# galvanika-board-2_0.net
KiCad netlist of a schematic drawn in EAGLE
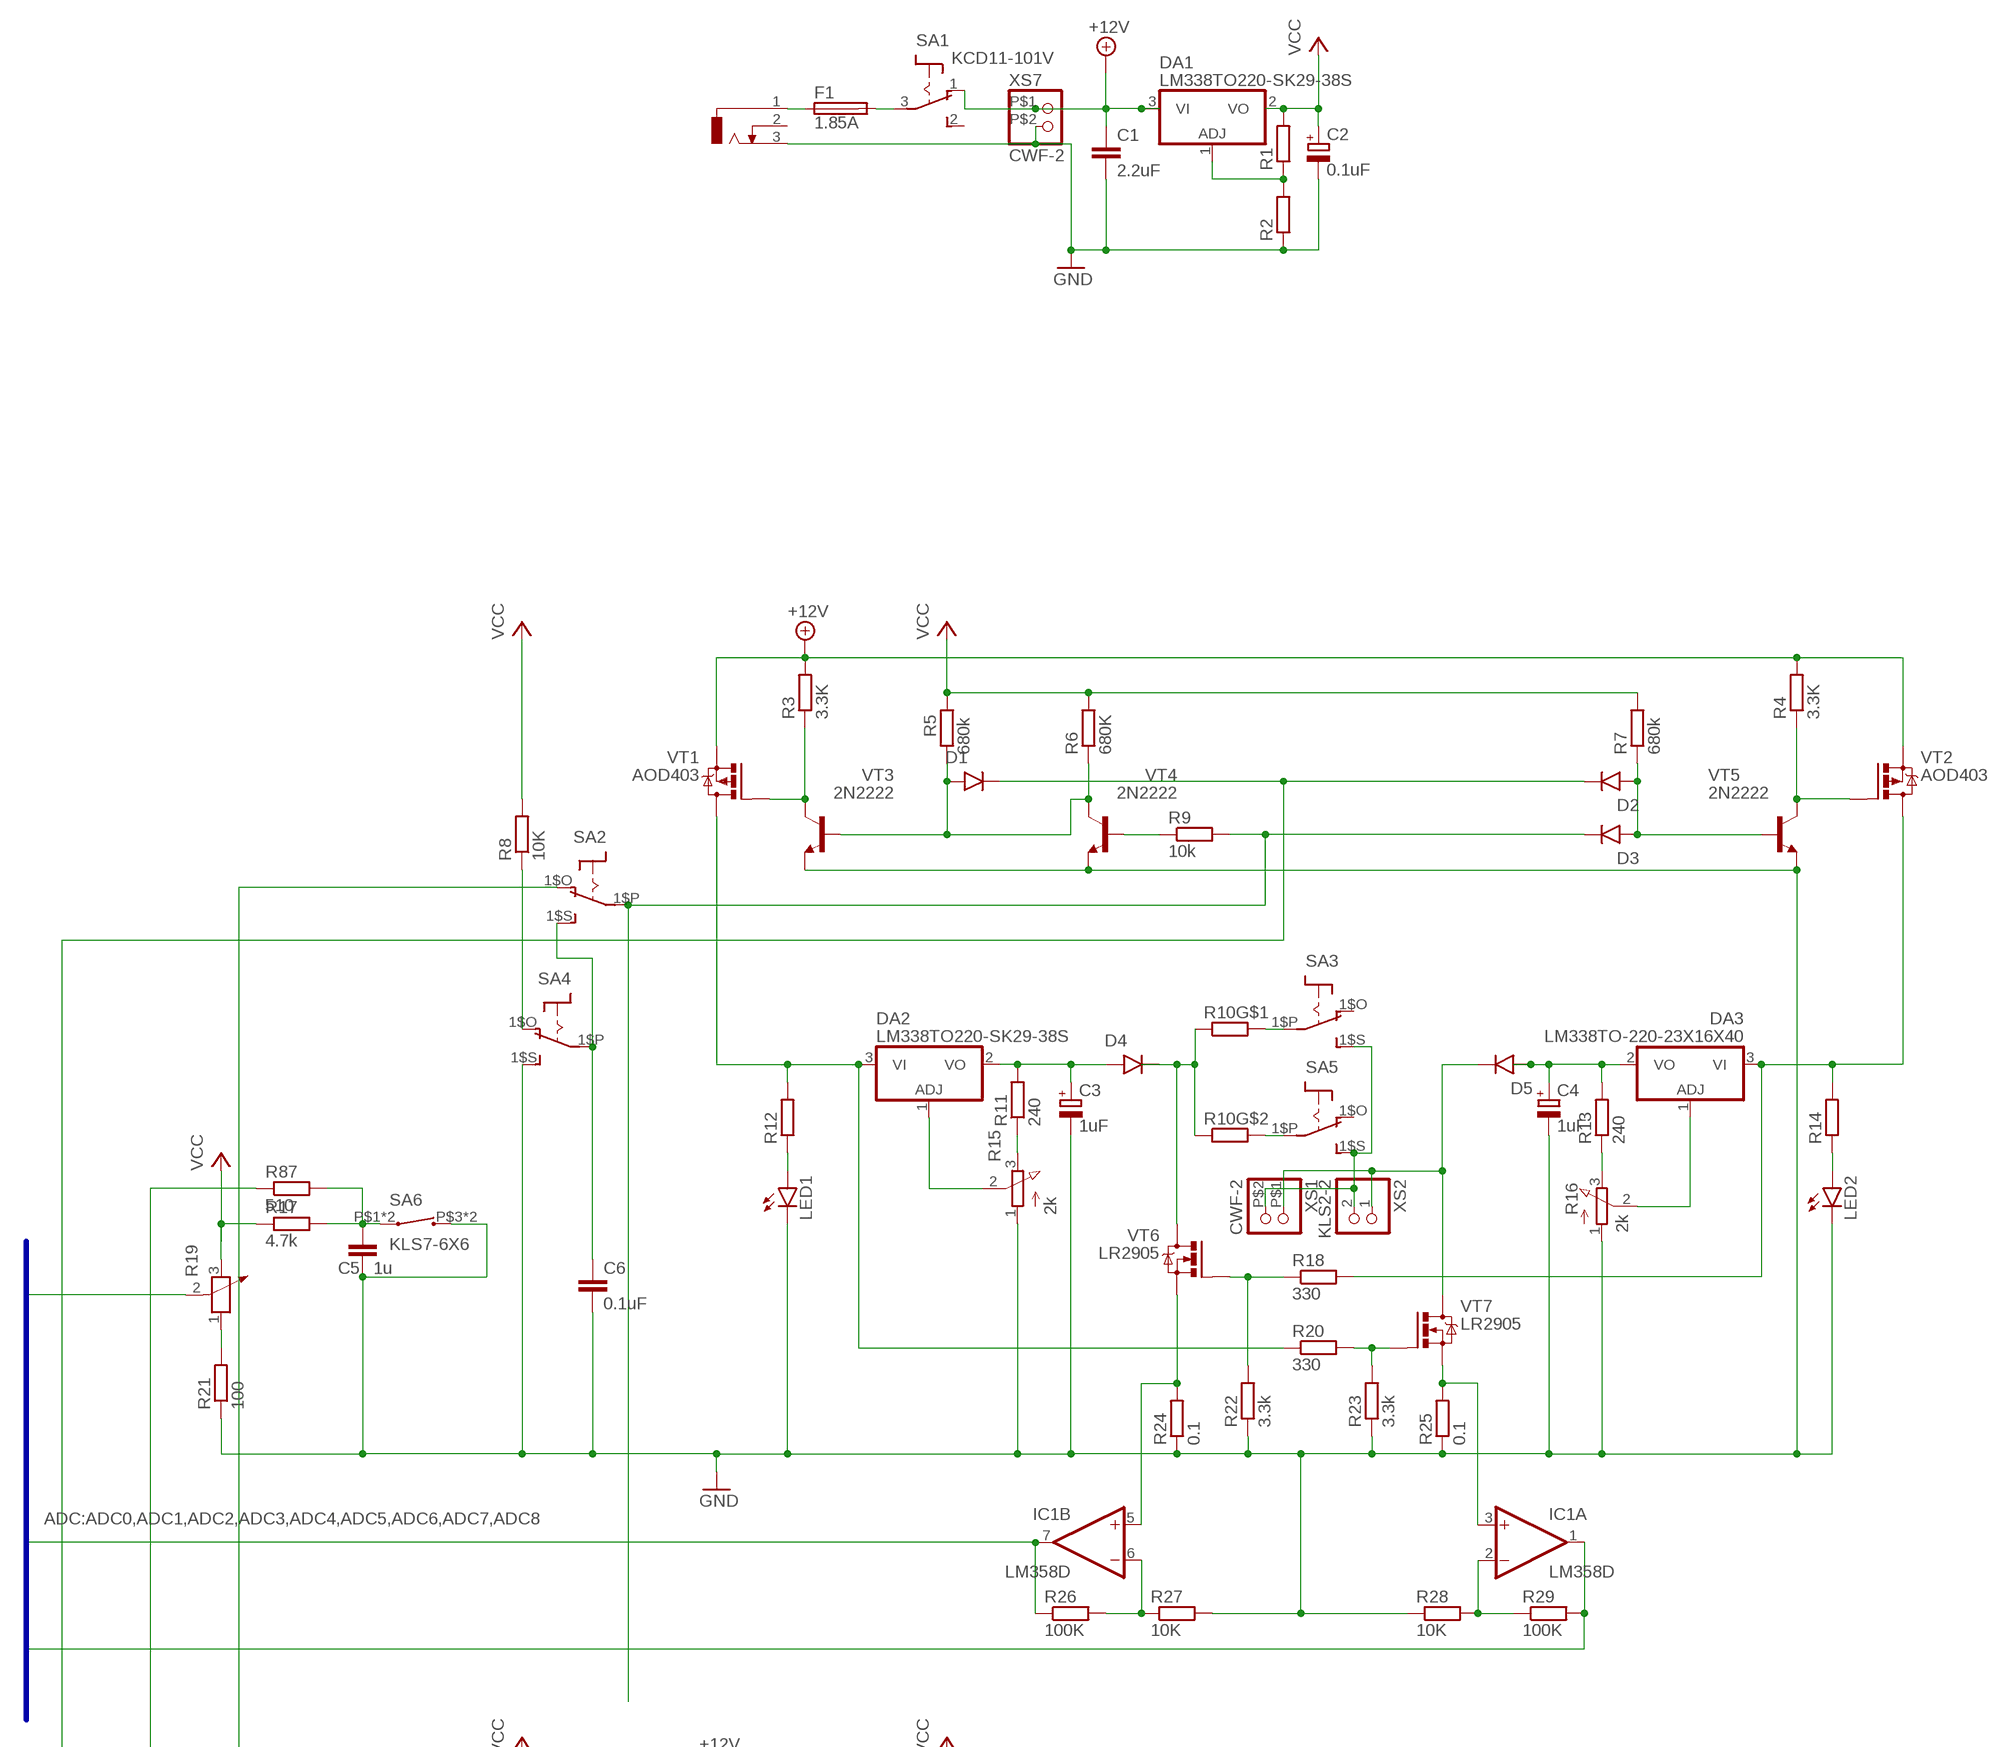
[diagram p0: schematic, sheet 1, part 1 of 2]
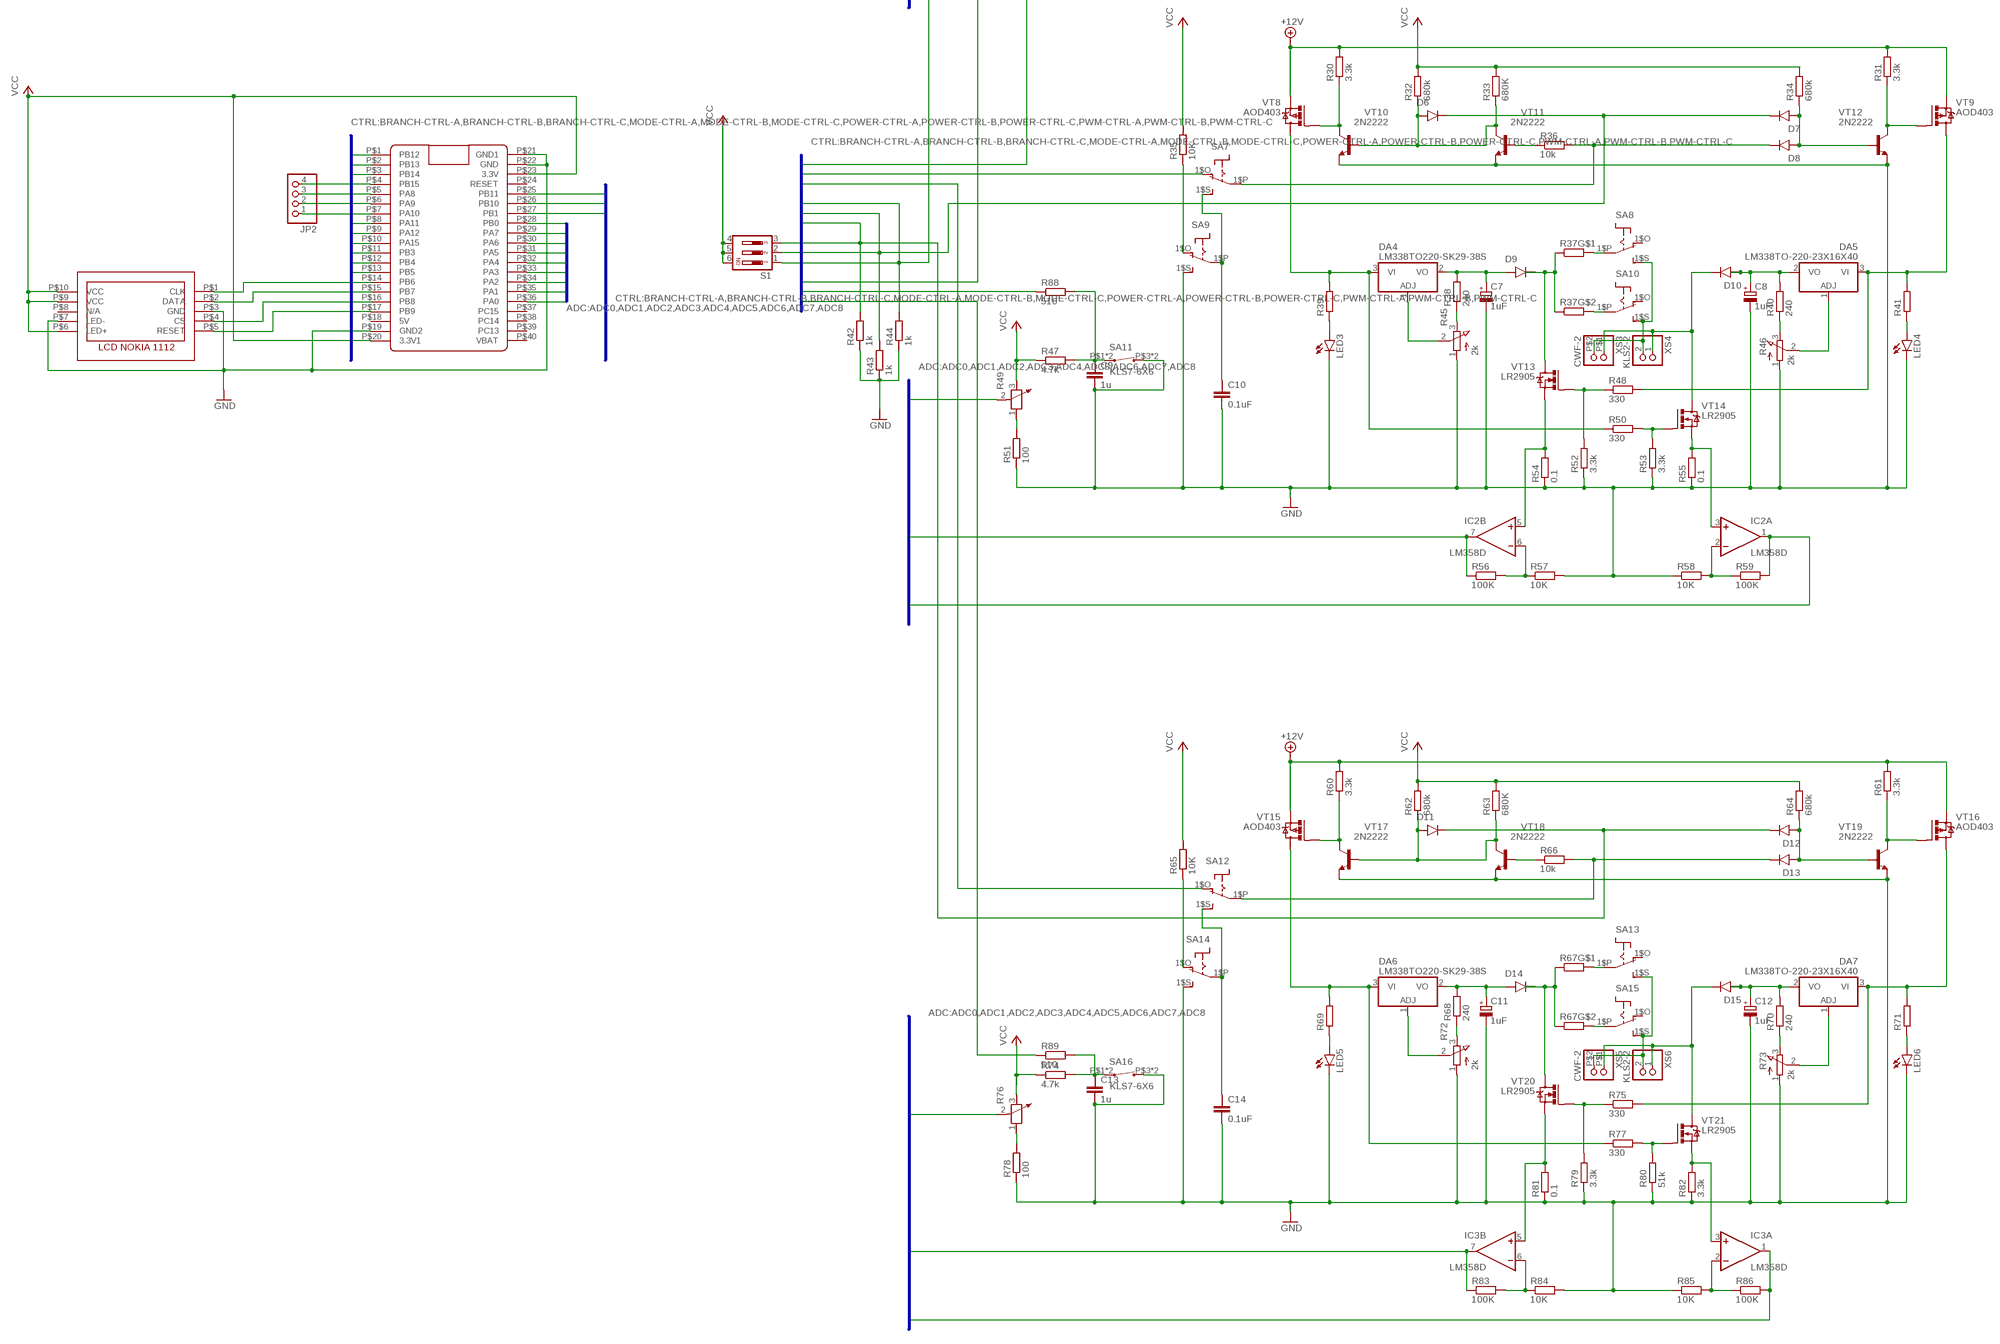
[diagram p1: schematic, sheet 1, part 2 of 2]

(export (version "E")
  (design (tool "Eeschema 10.0.6"))
  (components
    (comp (ref "C1")
      (value "2.2uF")
      (footprint "eagle-import:C025-025X050")
      (libsource (lib "eagle-import") (part "C-EU025-025X050"))
    )
    (comp (ref "C2")
      (value "0.1uF")
      (footprint "eagle-import:E2,5-5")
      (libsource (lib "eagle-import") (part "rcl_334_CPOL-EUE2.5-5"))
    )
    (comp (ref "C3")
      (value "1uF")
      (footprint "eagle-import:E5-4")
      (libsource (lib "eagle-import") (part "CPOL-EUE5-4"))
    )
    (comp (ref "C4")
      (value "1uF")
      (footprint "eagle-import:E5-4")
      (libsource (lib "eagle-import") (part "CPOL-EUE5-4"))
    )
    (comp (ref "C5")
      (value "1u")
      (footprint "eagle-import:C1206")
      (libsource (lib "eagle-import") (part "C-EUC1206"))
    )
    (comp (ref "C6")
      (value "0.1uF")
      (footprint "eagle-import:C1206")
      (libsource (lib "eagle-import") (part "C-EUC1206"))
    )
    (comp (ref "C7")
      (value "1uF")
      (footprint "eagle-import:E5-4")
      (libsource (lib "eagle-import") (part "CPOL-EUE5-4"))
    )
    (comp (ref "C8")
      (value "1uF")
      (footprint "eagle-import:E5-4")
      (libsource (lib "eagle-import") (part "CPOL-EUE5-4"))
    )
    (comp (ref "C9")
      (value "1u")
      (footprint "eagle-import:C1206")
      (libsource (lib "eagle-import") (part "C-EUC1206"))
    )
    (comp (ref "C10")
      (value "0.1uF")
      (footprint "eagle-import:C1206")
      (libsource (lib "eagle-import") (part "C-EUC1206"))
    )
    (comp (ref "C11")
      (value "1uF")
      (footprint "eagle-import:E5-4")
      (libsource (lib "eagle-import") (part "CPOL-EUE5-4"))
    )
    (comp (ref "C12")
      (value "1uF")
      (footprint "eagle-import:E5-4")
      (libsource (lib "eagle-import") (part "CPOL-EUE5-4"))
    )
    (comp (ref "C13")
      (value "1u")
      (footprint "eagle-import:C1206")
      (libsource (lib "eagle-import") (part "C-EUC1206"))
    )
    (comp (ref "C14")
      (value "0.1uF")
      (footprint "eagle-import:C1206")
      (libsource (lib "eagle-import") (part "C-EUC1206"))
    )
    (comp (ref "D1")
      (value "1N4001")
      (footprint "eagle-import:DO41-10")
      (libsource (lib "eagle-import") (part "1N4001"))
    )
    (comp (ref "D2")
      (value "1N4001")
      (footprint "eagle-import:DO41-10")
      (libsource (lib "eagle-import") (part "1N4001"))
    )
    (comp (ref "D3")
      (value "1N4001")
      (footprint "eagle-import:DO41-10")
      (libsource (lib "eagle-import") (part "1N4001"))
    )
    (comp (ref "D4")
      (value "1N4001")
      (footprint "eagle-import:DO41-10")
      (libsource (lib "eagle-import") (part "1N4001"))
    )
    (comp (ref "D5")
      (value "1N4001")
      (footprint "eagle-import:DO41-10")
      (libsource (lib "eagle-import") (part "1N4001"))
    )
    (comp (ref "D6")
      (value "1N4001")
      (footprint "eagle-import:DO41-10")
      (libsource (lib "eagle-import") (part "1N4001"))
    )
    (comp (ref "D7")
      (value "1N4001")
      (footprint "eagle-import:DO41-10")
      (libsource (lib "eagle-import") (part "1N4001"))
    )
    (comp (ref "D8")
      (value "1N4001")
      (footprint "eagle-import:DO41-10")
      (libsource (lib "eagle-import") (part "1N4001"))
    )
    (comp (ref "D9")
      (value "1N4001")
      (footprint "eagle-import:DO41-10")
      (libsource (lib "eagle-import") (part "1N4001"))
    )
    (comp (ref "D10")
      (value "1N4001")
      (footprint "eagle-import:DO41-10")
      (libsource (lib "eagle-import") (part "1N4001"))
    )
    (comp (ref "D11")
      (value "1N4001")
      (footprint "eagle-import:DO41-10")
      (libsource (lib "eagle-import") (part "1N4001"))
    )
    (comp (ref "D12")
      (value "1N4001")
      (footprint "eagle-import:DO41-10")
      (libsource (lib "eagle-import") (part "1N4001"))
    )
    (comp (ref "D13")
      (value "1N4001")
      (footprint "eagle-import:DO41-10")
      (libsource (lib "eagle-import") (part "1N4001"))
    )
    (comp (ref "D14")
      (value "1N4001")
      (footprint "eagle-import:DO41-10")
      (libsource (lib "eagle-import") (part "1N4001"))
    )
    (comp (ref "D15")
      (value "1N4001")
      (footprint "eagle-import:DO41-10")
      (libsource (lib "eagle-import") (part "1N4001"))
    )
    (comp (ref "DA1")
      (value "LM338TO220-SK29-38S")
      (footprint "eagle-import:TO220-SK29-38S")
      (libsource (lib "eagle-import") (part "LM338TO220-SK29-38S"))
    )
    (comp (ref "DA2")
      (value "LM338TO220-SK29-38S")
      (footprint "eagle-import:TO220-SK29-38S")
      (libsource (lib "eagle-import") (part "LM338TO220-SK29-38S"))
    )
    (comp (ref "DA3")
      (value "LM338TO-220-23X16X40")
      (footprint "eagle-import:TO220-23X16X40")
      (libsource (lib "eagle-import") (part "LM338TO-220-23X16X40"))
    )
    (comp (ref "DA4")
      (value "LM338TO220-SK29-38S")
      (footprint "eagle-import:TO220-SK29-38S")
      (libsource (lib "eagle-import") (part "LM338TO220-SK29-38S"))
    )
    (comp (ref "DA5")
      (value "LM338TO-220-23X16X40")
      (footprint "eagle-import:TO220-23X16X40")
      (libsource (lib "eagle-import") (part "LM338TO-220-23X16X40"))
    )
    (comp (ref "DA6")
      (value "LM338TO220-SK29-38S")
      (footprint "eagle-import:TO220-SK29-38S")
      (libsource (lib "eagle-import") (part "LM338TO220-SK29-38S"))
    )
    (comp (ref "DA7")
      (value "LM338TO-220-23X16X40")
      (footprint "eagle-import:TO220-23X16X40")
      (libsource (lib "eagle-import") (part "LM338TO-220-23X16X40"))
    )
    (comp (ref "DD1")
      (value "BLUE_PILL")
      (footprint "eagle-import:BLUE_PILL")
      (libsource (lib "eagle-import") (part "BLUE_PILL"))
    )
    (comp (ref "F1")
      (value "1.85A")
      (footprint "eagle-import:MF-R")
      (libsource (lib "eagle-import") (part "MF-R"))
    )
    (comp (ref "HG1")
      (value "WD-G0906WY-BOARD")
      (footprint "eagle-import:WD-G0906WY-BOARD")
      (libsource (lib "eagle-import") (part "WD-G0906WY-BOARD"))
    )
    (comp (ref "IC1")
      (value "LM358D")
      (footprint "eagle-import:SO08")
      (libsource (lib "eagle-import") (part "LM358D"))
    )
    (comp (ref "IC2")
      (value "LM358D")
      (footprint "eagle-import:SO08")
      (libsource (lib "eagle-import") (part "LM358D"))
    )
    (comp (ref "IC3")
      (value "LM358D")
      (footprint "eagle-import:SO08")
      (libsource (lib "eagle-import") (part "LM358D"))
    )
    (comp (ref "J1")
      (value "DCJ0303")
      (footprint "eagle-import:DCJ0303")
      (libsource (lib "eagle-import") (part "DCJ0303"))
    )
    (comp (ref "JP2")
      (value "PINHD-1X4")
      (footprint "eagle-import:1X04")
      (libsource (lib "eagle-import") (part "PINHD-1X4"))
    )
    (comp (ref "LED1")
      (value "LED3MM")
      (footprint "eagle-import:LED3MM")
      (libsource (lib "eagle-import") (part "LED3MM"))
    )
    (comp (ref "LED2")
      (value "LED3MM")
      (footprint "eagle-import:LED3MM")
      (libsource (lib "eagle-import") (part "LED3MM"))
    )
    (comp (ref "LED3")
      (value "LED3MM")
      (footprint "eagle-import:LED3MM")
      (libsource (lib "eagle-import") (part "LED3MM"))
    )
    (comp (ref "LED4")
      (value "LED3MM")
      (footprint "eagle-import:LED3MM")
      (libsource (lib "eagle-import") (part "LED3MM"))
    )
    (comp (ref "LED5")
      (value "LED3MM")
      (footprint "eagle-import:LED3MM")
      (libsource (lib "eagle-import") (part "LED3MM"))
    )
    (comp (ref "LED6")
      (value "LED3MM")
      (footprint "eagle-import:LED3MM")
      (libsource (lib "eagle-import") (part "LED3MM"))
    )
    (comp (ref "R1")
      (value "R-EU_0207/10")
      (footprint "eagle-import:0207_10")
      (libsource (lib "eagle-import") (part "R-EU_0207/10"))
    )
    (comp (ref "R2")
      (value "R-EU_0207/10")
      (footprint "eagle-import:0207_10")
      (libsource (lib "eagle-import") (part "R-EU_0207/10"))
    )
    (comp (ref "R3")
      (value "3.3K")
      (footprint "eagle-import:0207_10")
      (libsource (lib "eagle-import") (part "rcl_334_R-EU_0207/10"))
    )
    (comp (ref "R4")
      (value "3.3K")
      (footprint "eagle-import:0207_10")
      (libsource (lib "eagle-import") (part "rcl_334_R-EU_0207/10"))
    )
    (comp (ref "R5")
      (value "680k")
      (footprint "eagle-import:0207_10")
      (libsource (lib "eagle-import") (part "rcl_334_R-EU_0207/10"))
    )
    (comp (ref "R6")
      (value "680K")
      (footprint "eagle-import:0207_10")
      (libsource (lib "eagle-import") (part "rcl_334_R-EU_0207/10"))
    )
    (comp (ref "R7")
      (value "680k")
      (footprint "eagle-import:0207_10")
      (libsource (lib "eagle-import") (part "rcl_334_R-EU_0207/10"))
    )
    (comp (ref "R8")
      (value "10K")
      (footprint "eagle-import:0207_10")
      (libsource (lib "eagle-import") (part "rcl_334_R-EU_0207/10"))
    )
    (comp (ref "R9")
      (value "10k")
      (footprint "eagle-import:0207_10")
      (libsource (lib "eagle-import") (part "rcl_334_R-EU_0207/10"))
    )
    (comp (ref "R10")
      (value "SQP-5W-2")
      (footprint "eagle-import:SQP-5W-2")
      (libsource (lib "eagle-import") (part "SQP-5W-2"))
    )
    (comp (ref "R11")
      (value "240")
      (footprint "eagle-import:0207_10")
      (libsource (lib "eagle-import") (part "rcl_334_R-EU_0207/10"))
    )
    (comp (ref "R12")
      (value "R-EU_0207/10")
      (footprint "eagle-import:0207_10")
      (libsource (lib "eagle-import") (part "rcl_334_R-EU_0207/10"))
    )
    (comp (ref "R13")
      (value "240")
      (footprint "eagle-import:0207_10")
      (libsource (lib "eagle-import") (part "rcl_334_R-EU_0207/10"))
    )
    (comp (ref "R14")
      (value "R-EU_0207/10")
      (footprint "eagle-import:0207_10")
      (libsource (lib "eagle-import") (part "rcl_334_R-EU_0207/10"))
    )
    (comp (ref "R15")
      (value "2k")
      (footprint "eagle-import:3RP_1610N")
      (libsource (lib "eagle-import") (part "3RP/1610N"))
    )
    (comp (ref "R16")
      (value "2k")
      (footprint "eagle-import:3RP_1610N")
      (libsource (lib "eagle-import") (part "3RP/1610N"))
    )
    (comp (ref "R17")
      (value "4.7k")
      (footprint "eagle-import:R1206")
      (libsource (lib "eagle-import") (part "R-EU_R1206"))
    )
    (comp (ref "R18")
      (value "330")
      (footprint "eagle-import:0207_10")
      (libsource (lib "eagle-import") (part "rcl_334_R-EU_0207/10"))
    )
    (comp (ref "R19")
      (value "R0904N")
      (footprint "eagle-import:R0904N")
      (libsource (lib "eagle-import") (part "R0904N"))
    )
    (comp (ref "R20")
      (value "330")
      (footprint "eagle-import:0207_10")
      (libsource (lib "eagle-import") (part "rcl_334_R-EU_0207/10"))
    )
    (comp (ref "R21")
      (value "100")
      (footprint "eagle-import:R1206")
      (libsource (lib "eagle-import") (part "R-EU_R1206"))
    )
    (comp (ref "R22")
      (value "3.3k")
      (footprint "eagle-import:0207_10")
      (libsource (lib "eagle-import") (part "rcl_334_R-EU_0207/10"))
    )
    (comp (ref "R23")
      (value "3.3k")
      (footprint "eagle-import:0207_10")
      (libsource (lib "eagle-import") (part "rcl_334_R-EU_0207/10"))
    )
    (comp (ref "R24")
      (value "0.1")
      (footprint "eagle-import:0411_12")
      (libsource (lib "eagle-import") (part "rcl_334_R-EU_0411/12"))
    )
    (comp (ref "R25")
      (value "0.1")
      (footprint "eagle-import:0411_12")
      (libsource (lib "eagle-import") (part "rcl_334_R-EU_0411/12"))
    )
    (comp (ref "R26")
      (value "100K")
      (footprint "eagle-import:R1206")
      (libsource (lib "eagle-import") (part "rcl_334_R-EU_R1206"))
    )
    (comp (ref "R27")
      (value "10K")
      (footprint "eagle-import:R1206")
      (libsource (lib "eagle-import") (part "rcl_334_R-EU_R1206"))
    )
    (comp (ref "R28")
      (value "10K")
      (footprint "eagle-import:R1206")
      (libsource (lib "eagle-import") (part "rcl_334_R-EU_R1206"))
    )
    (comp (ref "R29")
      (value "100K")
      (footprint "eagle-import:R1206")
      (libsource (lib "eagle-import") (part "rcl_334_R-EU_R1206"))
    )
    (comp (ref "R30")
      (value "3.3k")
      (footprint "eagle-import:0207_10")
      (libsource (lib "eagle-import") (part "rcl_334_R-EU_0207/10"))
    )
    (comp (ref "R31")
      (value "3.3k")
      (footprint "eagle-import:0207_10")
      (libsource (lib "eagle-import") (part "rcl_334_R-EU_0207/10"))
    )
    (comp (ref "R32")
      (value "680k")
      (footprint "eagle-import:0207_10")
      (libsource (lib "eagle-import") (part "rcl_334_R-EU_0207/10"))
    )
    (comp (ref "R33")
      (value "680K")
      (footprint "eagle-import:0207_10")
      (libsource (lib "eagle-import") (part "rcl_334_R-EU_0207/10"))
    )
    (comp (ref "R34")
      (value "680k")
      (footprint "eagle-import:0207_10")
      (libsource (lib "eagle-import") (part "rcl_334_R-EU_0207/10"))
    )
    (comp (ref "R35")
      (value "10K")
      (footprint "eagle-import:0207_10")
      (libsource (lib "eagle-import") (part "rcl_334_R-EU_0207/10"))
    )
    (comp (ref "R36")
      (value "10k")
      (footprint "eagle-import:0207_10")
      (libsource (lib "eagle-import") (part "rcl_334_R-EU_0207/10"))
    )
    (comp (ref "R37")
      (value "SQP-5W-2")
      (footprint "eagle-import:SQP-5W-2")
      (libsource (lib "eagle-import") (part "SQP-5W-2"))
    )
    (comp (ref "R38")
      (value "240")
      (footprint "eagle-import:0207_10")
      (libsource (lib "eagle-import") (part "R-EU_0207/10"))
    )
    (comp (ref "R39")
      (value "R-EU_0207/10")
      (footprint "eagle-import:0207_10")
      (libsource (lib "eagle-import") (part "R-EU_0207/10"))
    )
    (comp (ref "R40")
      (value "240")
      (footprint "eagle-import:0207_10")
      (libsource (lib "eagle-import") (part "rcl_334_R-EU_0207/10"))
    )
    (comp (ref "R41")
      (value "R-EU_0207/10")
      (footprint "eagle-import:0207_10")
      (libsource (lib "eagle-import") (part "R-EU_0207/10"))
    )
    (comp (ref "R42")
      (value "1k")
      (footprint "eagle-import:R1206")
      (libsource (lib "eagle-import") (part "R-EU_R1206"))
    )
    (comp (ref "R43")
      (value "1k")
      (footprint "eagle-import:R1206")
      (libsource (lib "eagle-import") (part "R-EU_R1206"))
    )
    (comp (ref "R44")
      (value "1k")
      (footprint "eagle-import:R1206")
      (libsource (lib "eagle-import") (part "R-EU_R1206"))
    )
    (comp (ref "R45")
      (value "2k")
      (footprint "eagle-import:3RP_1610N")
      (libsource (lib "eagle-import") (part "3RP/1610N"))
    )
    (comp (ref "R46")
      (value "2k")
      (footprint "eagle-import:3RP_1610N")
      (libsource (lib "eagle-import") (part "3RP/1610N"))
    )
    (comp (ref "R47")
      (value "4.7k")
      (footprint "eagle-import:R1206")
      (libsource (lib "eagle-import") (part "R-EU_R1206"))
    )
    (comp (ref "R48")
      (value "330")
      (footprint "eagle-import:0207_10")
      (libsource (lib "eagle-import") (part "rcl_334_R-EU_0207/10"))
    )
    (comp (ref "R49")
      (value "R0904N")
      (footprint "eagle-import:R0904N")
      (libsource (lib "eagle-import") (part "R0904N"))
    )
    (comp (ref "R50")
      (value "330")
      (footprint "eagle-import:0207_10")
      (libsource (lib "eagle-import") (part "rcl_334_R-EU_0207/10"))
    )
    (comp (ref "R51")
      (value "100")
      (footprint "eagle-import:R1206")
      (libsource (lib "eagle-import") (part "R-EU_R1206"))
    )
    (comp (ref "R52")
      (value "3.3k")
      (footprint "eagle-import:0207_10")
      (libsource (lib "eagle-import") (part "rcl_334_R-EU_0207/10"))
    )
    (comp (ref "R53")
      (value "3.3k")
      (footprint "eagle-import:0207_10")
      (libsource (lib "eagle-import") (part "rcl_334_R-EU_0207/10"))
    )
    (comp (ref "R54")
      (value "0.1")
      (footprint "eagle-import:0411_12")
      (libsource (lib "eagle-import") (part "rcl_334_R-EU_0411/12"))
    )
    (comp (ref "R55")
      (value "0.1")
      (footprint "eagle-import:0411_12")
      (libsource (lib "eagle-import") (part "rcl_334_R-EU_0411/12"))
    )
    (comp (ref "R56")
      (value "100K")
      (footprint "eagle-import:R1206")
      (libsource (lib "eagle-import") (part "rcl_334_R-EU_R1206"))
    )
    (comp (ref "R57")
      (value "10K")
      (footprint "eagle-import:R1206")
      (libsource (lib "eagle-import") (part "rcl_334_R-EU_R1206"))
    )
    (comp (ref "R58")
      (value "10K")
      (footprint "eagle-import:R1206")
      (libsource (lib "eagle-import") (part "rcl_334_R-EU_R1206"))
    )
    (comp (ref "R59")
      (value "100K")
      (footprint "eagle-import:R1206")
      (libsource (lib "eagle-import") (part "rcl_334_R-EU_R1206"))
    )
    (comp (ref "R60")
      (value "3.3k")
      (footprint "eagle-import:0207_10")
      (libsource (lib "eagle-import") (part "rcl_334_R-EU_0207/10"))
    )
    (comp (ref "R61")
      (value "3.3k")
      (footprint "eagle-import:0207_10")
      (libsource (lib "eagle-import") (part "rcl_334_R-EU_0207/10"))
    )
    (comp (ref "R62")
      (value "680k")
      (footprint "eagle-import:0207_10")
      (libsource (lib "eagle-import") (part "rcl_334_R-EU_0207/10"))
    )
    (comp (ref "R63")
      (value "680K")
      (footprint "eagle-import:0207_10")
      (libsource (lib "eagle-import") (part "rcl_334_R-EU_0207/10"))
    )
    (comp (ref "R64")
      (value "680k")
      (footprint "eagle-import:0207_10")
      (libsource (lib "eagle-import") (part "rcl_334_R-EU_0207/10"))
    )
    (comp (ref "R65")
      (value "10K")
      (footprint "eagle-import:0207_10")
      (libsource (lib "eagle-import") (part "rcl_334_R-EU_0207/10"))
    )
    (comp (ref "R66")
      (value "10k")
      (footprint "eagle-import:0207_10")
      (libsource (lib "eagle-import") (part "rcl_334_R-EU_0207/10"))
    )
    (comp (ref "R67")
      (value "SQP-5W-2")
      (footprint "eagle-import:SQP-5W-2")
      (libsource (lib "eagle-import") (part "SQP-5W-2"))
    )
    (comp (ref "R68")
      (value "240")
      (footprint "eagle-import:0207_10")
      (libsource (lib "eagle-import") (part "rcl_334_R-EU_0207/10"))
    )
    (comp (ref "R69")
      (value "R-EU_0207/10")
      (footprint "eagle-import:0207_10")
      (libsource (lib "eagle-import") (part "rcl_334_R-EU_0207/10"))
    )
    (comp (ref "R70")
      (value "240")
      (footprint "eagle-import:0207_10")
      (libsource (lib "eagle-import") (part "rcl_334_R-EU_0207/10"))
    )
    (comp (ref "R71")
      (value "R-EU_0207/10")
      (footprint "eagle-import:0207_10")
      (libsource (lib "eagle-import") (part "rcl_334_R-EU_0207/10"))
    )
    (comp (ref "R72")
      (value "2k")
      (footprint "eagle-import:3RP_1610N")
      (libsource (lib "eagle-import") (part "3RP/1610N"))
    )
    (comp (ref "R73")
      (value "2k")
      (footprint "eagle-import:3RP_1610N")
      (libsource (lib "eagle-import") (part "3RP/1610N"))
    )
    (comp (ref "R74")
      (value "4.7k")
      (footprint "eagle-import:R1206")
      (libsource (lib "eagle-import") (part "R-EU_R1206"))
    )
    (comp (ref "R75")
      (value "330")
      (footprint "eagle-import:0207_10")
      (libsource (lib "eagle-import") (part "rcl_334_R-EU_0207/10"))
    )
    (comp (ref "R76")
      (value "R0904N")
      (footprint "eagle-import:R0904N")
      (libsource (lib "eagle-import") (part "R0904N"))
    )
    (comp (ref "R77")
      (value "330")
      (footprint "eagle-import:0207_10")
      (libsource (lib "eagle-import") (part "rcl_334_R-EU_0207/10"))
    )
    (comp (ref "R78")
      (value "100")
      (footprint "eagle-import:R1206")
      (libsource (lib "eagle-import") (part "R-EU_R1206"))
    )
    (comp (ref "R79")
      (value "3.3k")
      (footprint "eagle-import:0207_10")
      (libsource (lib "eagle-import") (part "rcl_334_R-EU_0207/10"))
    )
    (comp (ref "R80")
      (value "51k")
      (footprint "eagle-import:0207_10")
      (libsource (lib "eagle-import") (part "rcl_334_R-EU_0207/10"))
    )
    (comp (ref "R81")
      (value "0.1")
      (footprint "eagle-import:0411_12")
      (libsource (lib "eagle-import") (part "rcl_334_R-EU_0411/12"))
    )
    (comp (ref "R82")
      (value "3.3k")
      (footprint "eagle-import:0411_12")
      (libsource (lib "eagle-import") (part "rcl_334_R-EU_0411/12"))
    )
    (comp (ref "R83")
      (value "100K")
      (footprint "eagle-import:R1206")
      (libsource (lib "eagle-import") (part "rcl_334_R-EU_R1206"))
    )
    (comp (ref "R84")
      (value "10K")
      (footprint "eagle-import:R1206")
      (libsource (lib "eagle-import") (part "rcl_334_R-EU_R1206"))
    )
    (comp (ref "R85")
      (value "10K")
      (footprint "eagle-import:R1206")
      (libsource (lib "eagle-import") (part "rcl_334_R-EU_R1206"))
    )
    (comp (ref "R86")
      (value "100K")
      (footprint "eagle-import:R1206")
      (libsource (lib "eagle-import") (part "rcl_334_R-EU_R1206"))
    )
    (comp (ref "R87")
      (value "510")
      (footprint "eagle-import:R1206")
      (libsource (lib "eagle-import") (part "R-EU_R1206"))
    )
    (comp (ref "R88")
      (value "510")
      (footprint "eagle-import:R1206")
      (libsource (lib "eagle-import") (part "R-EU_R1206"))
    )
    (comp (ref "R89")
      (value "510")
      (footprint "eagle-import:R1206")
      (libsource (lib "eagle-import") (part "R-EU_R1206"))
    )
    (comp (ref "S1")
      (value "DS03")
      (footprint "eagle-import:DS-03")
      (libsource (lib "eagle-import") (part "DS03"))
    )
    (comp (ref "SA1")
      (value "KCD11-101V")
      (footprint "eagle-import:KCD11-101-V")
      (libsource (lib "eagle-import") (part "KCD11-101V"))
    )
    (comp (ref "SA2")
      (value "SS12D00DIP")
      (footprint "eagle-import:SS12D00")
      (libsource (lib "eagle-import") (part "SS12D00DIP"))
    )
    (comp (ref "SA3")
      (value "SS12D00DIP")
      (footprint "eagle-import:SS12D00")
      (libsource (lib "eagle-import") (part "SS12D00DIP"))
    )
    (comp (ref "SA4")
      (value "SS12D00DIP")
      (footprint "eagle-import:SS12D00")
      (libsource (lib "eagle-import") (part "SS12D00DIP"))
    )
    (comp (ref "SA5")
      (value "SS12D00DIP")
      (footprint "eagle-import:SS12D00")
      (libsource (lib "eagle-import") (part "SS12D00DIP"))
    )
    (comp (ref "SA6")
      (value "KLS7-6X6")
      (footprint "eagle-import:KLS7-6X6")
      (libsource (lib "eagle-import") (part "KLS7-6X6"))
    )
    (comp (ref "SA7")
      (value "SS12D00DIP")
      (footprint "eagle-import:SS12D00")
      (libsource (lib "eagle-import") (part "SS12D00DIP"))
    )
    (comp (ref "SA8")
      (value "SS12D00DIP")
      (footprint "eagle-import:SS12D00")
      (libsource (lib "eagle-import") (part "SS12D00DIP"))
    )
    (comp (ref "SA9")
      (value "SS12D00DIP")
      (footprint "eagle-import:SS12D00")
      (libsource (lib "eagle-import") (part "SS12D00DIP"))
    )
    (comp (ref "SA10")
      (value "SS12D00DIP")
      (footprint "eagle-import:SS12D00")
      (libsource (lib "eagle-import") (part "SS12D00DIP"))
    )
    (comp (ref "SA11")
      (value "KLS7-6X6")
      (footprint "eagle-import:KLS7-6X6")
      (libsource (lib "eagle-import") (part "KLS7-6X6"))
    )
    (comp (ref "SA12")
      (value "SS12D00DIP")
      (footprint "eagle-import:SS12D00")
      (libsource (lib "eagle-import") (part "SS12D00DIP"))
    )
    (comp (ref "SA13")
      (value "SS12D00DIP")
      (footprint "eagle-import:SS12D00")
      (libsource (lib "eagle-import") (part "SS12D00DIP"))
    )
    (comp (ref "SA14")
      (value "SS12D00DIP")
      (footprint "eagle-import:SS12D00")
      (libsource (lib "eagle-import") (part "SS12D00DIP"))
    )
    (comp (ref "SA15")
      (value "SS12D00DIP")
      (footprint "eagle-import:SS12D00")
      (libsource (lib "eagle-import") (part "SS12D00DIP"))
    )
    (comp (ref "SA16")
      (value "KLS7-6X6")
      (footprint "eagle-import:KLS7-6X6")
      (libsource (lib "eagle-import") (part "KLS7-6X6"))
    )
    (comp (ref "VT1")
      (value "AOD403")
      (footprint "eagle-import:TO252")
      (libsource (lib "eagle-import") (part "AOD403"))
    )
    (comp (ref "VT2")
      (value "AOD403")
      (footprint "eagle-import:TO252")
      (libsource (lib "eagle-import") (part "AOD403"))
    )
    (comp (ref "VT3")
      (value "2N2222")
      (footprint "eagle-import:TO92")
      (libsource (lib "eagle-import") (part "2N2222"))
    )
    (comp (ref "VT4")
      (value "2N2222")
      (footprint "eagle-import:TO92")
      (libsource (lib "eagle-import") (part "2N2222"))
    )
    (comp (ref "VT5")
      (value "2N2222")
      (footprint "eagle-import:TO92")
      (libsource (lib "eagle-import") (part "2N2222"))
    )
    (comp (ref "VT6")
      (value "LR2905")
      (footprint "eagle-import:TO252")
      (libsource (lib "eagle-import") (part "LR2905"))
    )
    (comp (ref "VT7")
      (value "LR2905")
      (footprint "eagle-import:TO252")
      (libsource (lib "eagle-import") (part "LR2905"))
    )
    (comp (ref "VT8")
      (value "AOD403")
      (footprint "eagle-import:TO252")
      (libsource (lib "eagle-import") (part "AOD403"))
    )
    (comp (ref "VT9")
      (value "AOD403")
      (footprint "eagle-import:TO252")
      (libsource (lib "eagle-import") (part "AOD403"))
    )
    (comp (ref "VT10")
      (value "2N2222")
      (footprint "eagle-import:TO92")
      (libsource (lib "eagle-import") (part "2N2222"))
    )
    (comp (ref "VT11")
      (value "2N2222")
      (footprint "eagle-import:TO92")
      (libsource (lib "eagle-import") (part "2N2222"))
    )
    (comp (ref "VT12")
      (value "2N2222")
      (footprint "eagle-import:TO92")
      (libsource (lib "eagle-import") (part "2N2222"))
    )
    (comp (ref "VT13")
      (value "LR2905")
      (footprint "eagle-import:TO252")
      (libsource (lib "eagle-import") (part "LR2905"))
    )
    (comp (ref "VT14")
      (value "LR2905")
      (footprint "eagle-import:TO252")
      (libsource (lib "eagle-import") (part "LR2905"))
    )
    (comp (ref "VT15")
      (value "AOD403")
      (footprint "eagle-import:TO252")
      (libsource (lib "eagle-import") (part "AOD403"))
    )
    (comp (ref "VT16")
      (value "AOD403")
      (footprint "eagle-import:TO252")
      (libsource (lib "eagle-import") (part "AOD403"))
    )
    (comp (ref "VT17")
      (value "2N2222")
      (footprint "eagle-import:TO92")
      (libsource (lib "eagle-import") (part "2N2222"))
    )
    (comp (ref "VT18")
      (value "2N2222")
      (footprint "eagle-import:TO92")
      (libsource (lib "eagle-import") (part "2N2222"))
    )
    (comp (ref "VT19")
      (value "2N2222")
      (footprint "eagle-import:TO92")
      (libsource (lib "eagle-import") (part "2N2222"))
    )
    (comp (ref "VT20")
      (value "LR2905")
      (footprint "eagle-import:TO252")
      (libsource (lib "eagle-import") (part "LR2905"))
    )
    (comp (ref "VT21")
      (value "LR2905")
      (footprint "eagle-import:TO252")
      (libsource (lib "eagle-import") (part "LR2905"))
    )
    (comp (ref "XS1")
      (value "CWF-2")
      (footprint "eagle-import:CWF-2")
      (libsource (lib "eagle-import") (part "CWF-2"))
    )
    (comp (ref "XS2")
      (value "KLS2-2")
      (footprint "eagle-import:KLS2-2")
      (libsource (lib "eagle-import") (part "KLS2-2"))
    )
    (comp (ref "XS3")
      (value "CWF-2")
      (footprint "eagle-import:CWF-2")
      (libsource (lib "eagle-import") (part "CWF-2"))
    )
    (comp (ref "XS4")
      (value "KLS2-2")
      (footprint "eagle-import:KLS2-2")
      (libsource (lib "eagle-import") (part "KLS2-2"))
    )
    (comp (ref "XS5")
      (value "CWF-2")
      (footprint "eagle-import:CWF-2")
      (libsource (lib "eagle-import") (part "CWF-2"))
    )
    (comp (ref "XS6")
      (value "KLS2-2")
      (footprint "eagle-import:KLS2-2")
      (libsource (lib "eagle-import") (part "KLS2-2"))
    )
    (comp (ref "XS7")
      (value "CWF-2")
      (footprint "eagle-import:CWF-2")
      (libsource (lib "eagle-import") (part "CWF-2"))
    )
  )
  (nets
    (net (code "3") (name "+12V") (class "Default")
      (node (ref "C1") (pin "1") (pinfunction "1_1") (pintype "passive"))
      (node (ref "DA1") (pin "3") (pinfunction "VI_3") (pintype "input"))
      (node (ref "R3") (pin "2") (pinfunction "2_2") (pintype "passive"))
      (node (ref "R30") (pin "2") (pinfunction "2_2") (pintype "passive"))
      (node (ref "R31") (pin "2") (pinfunction "2_2") (pintype "passive"))
      (node (ref "R4") (pin "2") (pinfunction "2_2") (pintype "passive"))
      (node (ref "R60") (pin "2") (pinfunction "2_2") (pintype "passive"))
      (node (ref "R61") (pin "2") (pinfunction "2_2") (pintype "passive"))
      (node (ref "SA1") (pin "1") (pinfunction "O_1") (pintype "passive"))
      (node (ref "VT1") (pin "2") (pinfunction "S_2") (pintype "passive"))
      (node (ref "VT15") (pin "2") (pinfunction "S_2") (pintype "passive"))
      (node (ref "VT16") (pin "2") (pinfunction "S_2") (pintype "passive"))
      (node (ref "VT2") (pin "2") (pinfunction "S_2") (pintype "passive"))
      (node (ref "VT8") (pin "2") (pinfunction "S_2") (pintype "passive"))
      (node (ref "VT9") (pin "2") (pinfunction "S_2") (pintype "passive"))
      (node (ref "XS7") (pin "P$1") (pinfunction "1_P$1") (pintype "passive"))
    )
    (net (code "4") (name "/ADC0") (class "Default")
      (node (ref "DD1") (pin "P$36") (pinfunction "PA0_P$36") (pintype "bidirectional"))
      (node (ref "R19") (pin "2") (pinfunction "3_2") (pintype "passive"))
    )
    (net (code "5") (name "/ADC1") (class "Default")
      (node (ref "DD1") (pin "P$35") (pinfunction "PA1_P$35") (pintype "bidirectional"))
      (node (ref "R49") (pin "2") (pinfunction "3_2") (pintype "passive"))
    )
    (net (code "6") (name "/ADC2") (class "Default")
      (node (ref "DD1") (pin "P$34") (pinfunction "PA2_P$34") (pintype "bidirectional"))
      (node (ref "IC1") (pin "7") (pinfunction "OUT_7") (pintype "output"))
      (node (ref "R26") (pin "1") (pinfunction "1_1") (pintype "passive"))
    )
    (net (code "7") (name "/ADC3") (class "Default")
      (node (ref "DD1") (pin "P$33") (pinfunction "PA3_P$33") (pintype "bidirectional"))
      (node (ref "IC1") (pin "1") (pinfunction "OUT_1") (pintype "output"))
      (node (ref "R29") (pin "2") (pinfunction "2_2") (pintype "passive"))
    )
    (net (code "8") (name "/ADC4") (class "Default")
      (node (ref "DD1") (pin "P$32") (pinfunction "PA4_P$32") (pintype "bidirectional"))
      (node (ref "R76") (pin "2") (pinfunction "3_2") (pintype "passive"))
    )
    (net (code "9") (name "/ADC5") (class "Default")
      (node (ref "DD1") (pin "P$31") (pinfunction "PA5_P$31") (pintype "bidirectional"))
      (node (ref "IC2") (pin "1") (pinfunction "OUT_1") (pintype "output"))
      (node (ref "R59") (pin "2") (pinfunction "2_2") (pintype "passive"))
    )
    (net (code "10") (name "/ADC6") (class "Default")
      (node (ref "DD1") (pin "P$30") (pinfunction "PA6_P$30") (pintype "bidirectional"))
      (node (ref "IC2") (pin "7") (pinfunction "OUT_7") (pintype "output"))
      (node (ref "R56") (pin "1") (pinfunction "1_1") (pintype "passive"))
    )
    (net (code "11") (name "/ADC7") (class "Default")
      (node (ref "DD1") (pin "P$29") (pinfunction "PA7_P$29") (pintype "bidirectional"))
      (node (ref "IC3") (pin "7") (pinfunction "OUT_7") (pintype "output"))
      (node (ref "R83") (pin "1") (pinfunction "1_1") (pintype "passive"))
    )
    (net (code "12") (name "/ADC8") (class "Default")
      (node (ref "DD1") (pin "P$28") (pinfunction "PB0_P$28") (pintype "bidirectional"))
      (node (ref "IC3") (pin "1") (pinfunction "OUT_1") (pintype "output"))
      (node (ref "R86") (pin "2") (pinfunction "2_2") (pintype "passive"))
    )
    (net (code "13") (name "/BRANCH-CTRL-A") (class "Default")
      (node (ref "D3") (pin "C") (pinfunction "CATHODE_C") (pintype "passive"))
      (node (ref "DD1") (pin "P$10") (pinfunction "PA15_P$10") (pintype "bidirectional"))
      (node (ref "R9") (pin "2") (pinfunction "2_2") (pintype "passive"))
      (node (ref "SA2") (pin "1$P") (pinfunction "P_1$P") (pintype "passive"))
    )
    (net (code "14") (name "/BRANCH-CTRL-B") (class "Default")
      (node (ref "D8") (pin "C") (pinfunction "CATHODE_C") (pintype "passive"))
      (node (ref "DD1") (pin "P$9") (pinfunction "PA12_P$9") (pintype "bidirectional"))
      (node (ref "R36") (pin "2") (pinfunction "2_2") (pintype "passive"))
      (node (ref "SA7") (pin "1$P") (pinfunction "P_1$P") (pintype "passive"))
    )
    (net (code "15") (name "/BRANCH-CTRL-C") (class "Default")
      (node (ref "D13") (pin "C") (pinfunction "CATHODE_C") (pintype "passive"))
      (node (ref "DD1") (pin "P$8") (pinfunction "PA11_P$8") (pintype "bidirectional"))
      (node (ref "R66") (pin "2") (pinfunction "2_2") (pintype "passive"))
      (node (ref "SA12") (pin "1$P") (pinfunction "P_1$P") (pintype "passive"))
    )
    (net (code "16") (name "/MODE-CTRL-A") (class "Default")
      (node (ref "DD1") (pin "P$13") (pinfunction "PB5_P$13") (pintype "bidirectional"))
      (node (ref "R87") (pin "1") (pinfunction "1_1") (pintype "passive"))
    )
    (net (code "17") (name "/MODE-CTRL-B") (class "Default")
      (node (ref "DD1") (pin "P$12") (pinfunction "PB4_P$12") (pintype "bidirectional"))
      (node (ref "R88") (pin "1") (pinfunction "1_1") (pintype "passive"))
    )
    (net (code "18") (name "/MODE-CTRL-C") (class "Default")
      (node (ref "DD1") (pin "P$11") (pinfunction "PB3_P$11") (pintype "bidirectional"))
      (node (ref "R89") (pin "1") (pinfunction "1_1") (pintype "passive"))
    )
    (net (code "19") (name "/POWER-CTRL-A") (class "Default")
      (node (ref "D1") (pin "C") (pinfunction "CATHODE_C") (pintype "passive"))
      (node (ref "D2") (pin "C") (pinfunction "CATHODE_C") (pintype "passive"))
      (node (ref "DD1") (pin "P$27") (pinfunction "PB1_P$27") (pintype "bidirectional"))
      (node (ref "R44") (pin "2") (pinfunction "2_2") (pintype "passive"))
      (node (ref "S1") (pin "1") (pinfunction "1_1") (pintype "passive"))
    )
    (net (code "20") (name "/POWER-CTRL-B") (class "Default")
      (node (ref "D6") (pin "C") (pinfunction "CATHODE_C") (pintype "passive"))
      (node (ref "D7") (pin "C") (pinfunction "CATHODE_C") (pintype "passive"))
      (node (ref "DD1") (pin "P$26") (pinfunction "PB10_P$26") (pintype "bidirectional"))
      (node (ref "R43") (pin "2") (pinfunction "2_2") (pintype "passive"))
      (node (ref "S1") (pin "2") (pinfunction "2_2") (pintype "passive"))
    )
    (net (code "21") (name "/POWER-CTRL-C") (class "Default")
      (node (ref "D11") (pin "C") (pinfunction "CATHODE_C") (pintype "passive"))
      (node (ref "D12") (pin "C") (pinfunction "CATHODE_C") (pintype "passive"))
      (node (ref "DD1") (pin "P$25") (pinfunction "PB11_P$25") (pintype "bidirectional"))
      (node (ref "R42") (pin "2") (pinfunction "2_2") (pintype "passive"))
      (node (ref "S1") (pin "3") (pinfunction "3_3") (pintype "passive"))
    )
    (net (code "22") (name "/PWM-CTRL-A") (class "Default")
      (node (ref "DD1") (pin "P$2") (pinfunction "PB13_P$2") (pintype "bidirectional"))
      (node (ref "SA2") (pin "1$O") (pinfunction "O_1$O") (pintype "passive"))
    )
    (net (code "23") (name "/PWM-CTRL-B") (class "Default")
      (node (ref "DD1") (pin "P$3") (pinfunction "PB14_P$3") (pintype "bidirectional"))
      (node (ref "SA7") (pin "1$O") (pinfunction "O_1$O") (pintype "passive"))
    )
    (net (code "24") (name "/PWM-CTRL-C") (class "Default")
      (node (ref "DD1") (pin "P$1") (pinfunction "PB12_P$1") (pintype "bidirectional"))
      (node (ref "SA12") (pin "1$O") (pinfunction "O_1$O") (pintype "passive"))
    )
    (net (code "27") (name "GND") (class "Default")
      (node (ref "C1") (pin "2") (pinfunction "2_2") (pintype "passive"))
      (node (ref "C10") (pin "2") (pinfunction "2_2") (pintype "passive"))
      (node (ref "C11") (pin "-") (pinfunction "-_-") (pintype "passive"))
      (node (ref "C12") (pin "-") (pinfunction "-_-") (pintype "passive"))
      (node (ref "C13") (pin "2") (pinfunction "2_2") (pintype "passive"))
      (node (ref "C14") (pin "2") (pinfunction "2_2") (pintype "passive"))
      (node (ref "C2") (pin "-") (pinfunction "-_-") (pintype "passive"))
      (node (ref "C3") (pin "-") (pinfunction "-_-") (pintype "passive"))
      (node (ref "C4") (pin "-") (pinfunction "-_-") (pintype "passive"))
      (node (ref "C5") (pin "2") (pinfunction "2_2") (pintype "passive"))
      (node (ref "C6") (pin "2") (pinfunction "2_2") (pintype "passive"))
      (node (ref "C7") (pin "-") (pinfunction "-_-") (pintype "passive"))
      (node (ref "C8") (pin "-") (pinfunction "-_-") (pintype "passive"))
      (node (ref "C9") (pin "2") (pinfunction "2_2") (pintype "passive"))
      (node (ref "DD1") (pin "P$19") (pinfunction "GND2_P$19") (pintype "bidirectional"))
      (node (ref "DD1") (pin "P$21") (pinfunction "GND1_P$21") (pintype "power_in"))
      (node (ref "DD1") (pin "P$22") (pinfunction "GND_P$22") (pintype "bidirectional"))
      (node (ref "HG1") (pin "P$3") (pinfunction "GND_P$3") (pintype "bidirectional"))
      (node (ref "HG1") (pin "P$7") (pinfunction "LED-_P$7") (pintype "bidirectional"))
      (node (ref "J1") (pin "3") (pinfunction "3_3") (pintype "passive"))
      (node (ref "LED1") (pin "K") (pinfunction "C_K") (pintype "passive"))
      (node (ref "LED2") (pin "K") (pinfunction "C_K") (pintype "passive"))
      (node (ref "LED3") (pin "K") (pinfunction "C_K") (pintype "passive"))
      (node (ref "LED4") (pin "K") (pinfunction "C_K") (pintype "passive"))
      (node (ref "LED5") (pin "K") (pinfunction "C_K") (pintype "passive"))
      (node (ref "LED6") (pin "K") (pinfunction "C_K") (pintype "passive"))
      (node (ref "R15") (pin "1") (pinfunction "A_1") (pintype "passive"))
      (node (ref "R16") (pin "1") (pinfunction "A_1") (pintype "passive"))
      (node (ref "R2") (pin "1") (pinfunction "1_1") (pintype "passive"))
      (node (ref "R21") (pin "1") (pinfunction "1_1") (pintype "passive"))
      (node (ref "R22") (pin "1") (pinfunction "1_1") (pintype "passive"))
      (node (ref "R23") (pin "1") (pinfunction "1_1") (pintype "passive"))
      (node (ref "R24") (pin "1") (pinfunction "1_1") (pintype "passive"))
      (node (ref "R25") (pin "1") (pinfunction "1_1") (pintype "passive"))
      (node (ref "R27") (pin "2") (pinfunction "2_2") (pintype "passive"))
      (node (ref "R28") (pin "1") (pinfunction "1_1") (pintype "passive"))
      (node (ref "R42") (pin "1") (pinfunction "1_1") (pintype "passive"))
      (node (ref "R43") (pin "1") (pinfunction "1_1") (pintype "passive"))
      (node (ref "R44") (pin "1") (pinfunction "1_1") (pintype "passive"))
      (node (ref "R45") (pin "1") (pinfunction "A_1") (pintype "passive"))
      (node (ref "R46") (pin "1") (pinfunction "A_1") (pintype "passive"))
      (node (ref "R51") (pin "1") (pinfunction "1_1") (pintype "passive"))
      (node (ref "R52") (pin "1") (pinfunction "1_1") (pintype "passive"))
      (node (ref "R53") (pin "1") (pinfunction "1_1") (pintype "passive"))
      (node (ref "R54") (pin "1") (pinfunction "1_1") (pintype "passive"))
      (node (ref "R55") (pin "1") (pinfunction "1_1") (pintype "passive"))
      (node (ref "R57") (pin "2") (pinfunction "2_2") (pintype "passive"))
      (node (ref "R58") (pin "1") (pinfunction "1_1") (pintype "passive"))
      (node (ref "R72") (pin "1") (pinfunction "A_1") (pintype "passive"))
      (node (ref "R73") (pin "1") (pinfunction "A_1") (pintype "passive"))
      (node (ref "R78") (pin "1") (pinfunction "1_1") (pintype "passive"))
      (node (ref "R79") (pin "1") (pinfunction "1_1") (pintype "passive"))
      (node (ref "R80") (pin "1") (pinfunction "1_1") (pintype "passive"))
      (node (ref "R81") (pin "1") (pinfunction "1_1") (pintype "passive"))
      (node (ref "R82") (pin "1") (pinfunction "1_1") (pintype "passive"))
      (node (ref "R84") (pin "2") (pinfunction "2_2") (pintype "passive"))
      (node (ref "R85") (pin "1") (pinfunction "1_1") (pintype "passive"))
      (node (ref "SA11") (pin "P$3") (pinfunction "2_P$3") (pintype "passive"))
      (node (ref "SA11") (pin "P$4") (pinfunction "2_P$4") (pintype "passive"))
      (node (ref "SA14") (pin "1$S") (pinfunction "S_1$S") (pintype "passive"))
      (node (ref "SA16") (pin "P$3") (pinfunction "2_P$3") (pintype "passive"))
      (node (ref "SA16") (pin "P$4") (pinfunction "2_P$4") (pintype "passive"))
      (node (ref "SA4") (pin "1$S") (pinfunction "S_1$S") (pintype "passive"))
      (node (ref "SA6") (pin "P$3") (pinfunction "2_P$3") (pintype "passive"))
      (node (ref "SA6") (pin "P$4") (pinfunction "2_P$4") (pintype "passive"))
      (node (ref "SA9") (pin "1$S") (pinfunction "S_1$S") (pintype "passive"))
      (node (ref "VT10") (pin "3") (pinfunction "E_3") (pintype "passive"))
      (node (ref "VT11") (pin "3") (pinfunction "E_3") (pintype "passive"))
      (node (ref "VT12") (pin "3") (pinfunction "E_3") (pintype "passive"))
      (node (ref "VT17") (pin "3") (pinfunction "E_3") (pintype "passive"))
      (node (ref "VT18") (pin "3") (pinfunction "E_3") (pintype "passive"))
      (node (ref "VT19") (pin "3") (pinfunction "E_3") (pintype "passive"))
      (node (ref "VT3") (pin "3") (pinfunction "E_3") (pintype "passive"))
      (node (ref "VT4") (pin "3") (pinfunction "E_3") (pintype "passive"))
      (node (ref "VT5") (pin "3") (pinfunction "E_3") (pintype "passive"))
      (node (ref "XS7") (pin "P$2") (pinfunction "2_P$2") (pintype "passive"))
    )
    (net (code "28") (name "Net-(C5-Pad1)") (class "Default")
      (node (ref "C5") (pin "1") (pinfunction "1_1") (pintype "passive"))
      (node (ref "R17") (pin "2") (pinfunction "2_2") (pintype "passive"))
      (node (ref "R87") (pin "2") (pinfunction "2_2") (pintype "passive"))
      (node (ref "SA6") (pin "P$1") (pinfunction "1_P$1") (pintype "passive"))
      (node (ref "SA6") (pin "P$2") (pinfunction "1_P$2") (pintype "passive"))
    )
    (net (code "29") (name "Net-(C9-Pad1)") (class "Default")
      (node (ref "C9") (pin "1") (pinfunction "1_1") (pintype "passive"))
      (node (ref "R47") (pin "2") (pinfunction "2_2") (pintype "passive"))
      (node (ref "R88") (pin "2") (pinfunction "2_2") (pintype "passive"))
      (node (ref "SA11") (pin "P$1") (pinfunction "1_P$1") (pintype "passive"))
      (node (ref "SA11") (pin "P$2") (pinfunction "1_P$2") (pintype "passive"))
    )
    (net (code "30") (name "Net-(C13-Pad1)") (class "Default")
      (node (ref "C13") (pin "1") (pinfunction "1_1") (pintype "passive"))
      (node (ref "R74") (pin "2") (pinfunction "2_2") (pintype "passive"))
      (node (ref "R89") (pin "2") (pinfunction "2_2") (pintype "passive"))
      (node (ref "SA16") (pin "P$1") (pinfunction "1_P$1") (pintype "passive"))
      (node (ref "SA16") (pin "P$2") (pinfunction "1_P$2") (pintype "passive"))
    )
    (net (code "31") (name "Net-(D1-ANODE)") (class "Default")
      (node (ref "D1") (pin "A") (pinfunction "ANODE_A") (pintype "passive"))
      (node (ref "R5") (pin "1") (pinfunction "1_1") (pintype "passive"))
      (node (ref "R6") (pin "1") (pinfunction "1_1") (pintype "passive"))
      (node (ref "VT3") (pin "2") (pinfunction "B_2") (pintype "passive"))
      (node (ref "VT4") (pin "1") (pinfunction "C_1") (pintype "passive"))
    )
    (net (code "32") (name "Net-(D2-ANODE)") (class "Default")
      (node (ref "D2") (pin "A") (pinfunction "ANODE_A") (pintype "passive"))
      (node (ref "D3") (pin "A") (pinfunction "ANODE_A") (pintype "passive"))
      (node (ref "R7") (pin "1") (pinfunction "1_1") (pintype "passive"))
      (node (ref "VT5") (pin "2") (pinfunction "B_2") (pintype "passive"))
    )
    (net (code "33") (name "Net-(D4-ANODE)") (class "Default")
      (node (ref "C3") (pin "+") (pinfunction "+_+") (pintype "passive"))
      (node (ref "D4") (pin "A") (pinfunction "ANODE_A") (pintype "passive"))
      (node (ref "DA2") (pin "2") (pinfunction "VO_2") (pintype "passive"))
      (node (ref "R11") (pin "2") (pinfunction "2_2") (pintype "passive"))
    )
    (net (code "34") (name "Net-(D4-CATHODE)") (class "Default")
      (node (ref "D4") (pin "C") (pinfunction "CATHODE_C") (pintype "passive"))
      (node (ref "R10") (pin "1") (pinfunction "1_1") (pintype "passive"))
      (node (ref "R10") (pin "3") (pinfunction "1_3") (pintype "passive"))
      (node (ref "VT6") (pin "3") (pinfunction "D_3") (pintype "passive"))
    )
    (net (code "35") (name "Net-(D5-ANODE)") (class "Default")
      (node (ref "C4") (pin "+") (pinfunction "+_+") (pintype "passive"))
      (node (ref "D5") (pin "A") (pinfunction "ANODE_A") (pintype "passive"))
      (node (ref "DA3") (pin "2") (pinfunction "VO_2") (pintype "passive"))
      (node (ref "R13") (pin "2") (pinfunction "2_2") (pintype "passive"))
    )
    (net (code "36") (name "Net-(D5-CATHODE)") (class "Default")
      (node (ref "D5") (pin "C") (pinfunction "CATHODE_C") (pintype "passive"))
      (node (ref "VT7") (pin "3") (pinfunction "D_3") (pintype "passive"))
      (node (ref "XS1") (pin "P$1") (pinfunction "1_P$1") (pintype "passive"))
      (node (ref "XS2") (pin "1") (pinfunction "1_1") (pintype "passive"))
    )
    (net (code "37") (name "Net-(D6-ANODE)") (class "Default")
      (node (ref "D6") (pin "A") (pinfunction "ANODE_A") (pintype "passive"))
      (node (ref "R32") (pin "1") (pinfunction "1_1") (pintype "passive"))
      (node (ref "R33") (pin "1") (pinfunction "1_1") (pintype "passive"))
      (node (ref "VT10") (pin "2") (pinfunction "B_2") (pintype "passive"))
      (node (ref "VT11") (pin "1") (pinfunction "C_1") (pintype "passive"))
    )
    (net (code "38") (name "Net-(D7-ANODE)") (class "Default")
      (node (ref "D7") (pin "A") (pinfunction "ANODE_A") (pintype "passive"))
      (node (ref "D8") (pin "A") (pinfunction "ANODE_A") (pintype "passive"))
      (node (ref "R34") (pin "1") (pinfunction "1_1") (pintype "passive"))
      (node (ref "VT12") (pin "2") (pinfunction "B_2") (pintype "passive"))
    )
    (net (code "39") (name "Net-(D9-ANODE)") (class "Default")
      (node (ref "C7") (pin "+") (pinfunction "+_+") (pintype "passive"))
      (node (ref "D9") (pin "A") (pinfunction "ANODE_A") (pintype "passive"))
      (node (ref "DA4") (pin "2") (pinfunction "VO_2") (pintype "passive"))
      (node (ref "R38") (pin "2") (pinfunction "2_2") (pintype "passive"))
    )
    (net (code "40") (name "Net-(D9-CATHODE)") (class "Default")
      (node (ref "D9") (pin "C") (pinfunction "CATHODE_C") (pintype "passive"))
      (node (ref "R37") (pin "1") (pinfunction "1_1") (pintype "passive"))
      (node (ref "R37") (pin "3") (pinfunction "1_3") (pintype "passive"))
      (node (ref "VT13") (pin "3") (pinfunction "D_3") (pintype "passive"))
    )
    (net (code "41") (name "Net-(D10-ANODE)") (class "Default")
      (node (ref "C8") (pin "+") (pinfunction "+_+") (pintype "passive"))
      (node (ref "D10") (pin "A") (pinfunction "ANODE_A") (pintype "passive"))
      (node (ref "DA5") (pin "2") (pinfunction "VO_2") (pintype "passive"))
      (node (ref "R40") (pin "2") (pinfunction "2_2") (pintype "passive"))
    )
    (net (code "42") (name "Net-(D10-CATHODE)") (class "Default")
      (node (ref "D10") (pin "C") (pinfunction "CATHODE_C") (pintype "passive"))
      (node (ref "VT14") (pin "3") (pinfunction "D_3") (pintype "passive"))
      (node (ref "XS3") (pin "P$1") (pinfunction "1_P$1") (pintype "passive"))
      (node (ref "XS4") (pin "1") (pinfunction "1_1") (pintype "passive"))
    )
    (net (code "43") (name "Net-(D11-ANODE)") (class "Default")
      (node (ref "D11") (pin "A") (pinfunction "ANODE_A") (pintype "passive"))
      (node (ref "R62") (pin "1") (pinfunction "1_1") (pintype "passive"))
      (node (ref "R63") (pin "1") (pinfunction "1_1") (pintype "passive"))
      (node (ref "VT17") (pin "2") (pinfunction "B_2") (pintype "passive"))
      (node (ref "VT18") (pin "1") (pinfunction "C_1") (pintype "passive"))
    )
    (net (code "44") (name "Net-(D12-ANODE)") (class "Default")
      (node (ref "D12") (pin "A") (pinfunction "ANODE_A") (pintype "passive"))
      (node (ref "D13") (pin "A") (pinfunction "ANODE_A") (pintype "passive"))
      (node (ref "R64") (pin "1") (pinfunction "1_1") (pintype "passive"))
      (node (ref "VT19") (pin "2") (pinfunction "B_2") (pintype "passive"))
    )
    (net (code "45") (name "Net-(D14-ANODE)") (class "Default")
      (node (ref "C11") (pin "+") (pinfunction "+_+") (pintype "passive"))
      (node (ref "D14") (pin "A") (pinfunction "ANODE_A") (pintype "passive"))
      (node (ref "DA6") (pin "2") (pinfunction "VO_2") (pintype "passive"))
      (node (ref "R68") (pin "2") (pinfunction "2_2") (pintype "passive"))
    )
    (net (code "46") (name "Net-(D14-CATHODE)") (class "Default")
      (node (ref "D14") (pin "C") (pinfunction "CATHODE_C") (pintype "passive"))
      (node (ref "R67") (pin "1") (pinfunction "1_1") (pintype "passive"))
      (node (ref "R67") (pin "3") (pinfunction "1_3") (pintype "passive"))
      (node (ref "VT20") (pin "3") (pinfunction "D_3") (pintype "passive"))
    )
    (net (code "47") (name "Net-(D15-ANODE)") (class "Default")
      (node (ref "C12") (pin "+") (pinfunction "+_+") (pintype "passive"))
      (node (ref "D15") (pin "A") (pinfunction "ANODE_A") (pintype "passive"))
      (node (ref "DA7") (pin "2") (pinfunction "VO_2") (pintype "passive"))
      (node (ref "R70") (pin "2") (pinfunction "2_2") (pintype "passive"))
    )
    (net (code "48") (name "Net-(D15-CATHODE)") (class "Default")
      (node (ref "D15") (pin "C") (pinfunction "CATHODE_C") (pintype "passive"))
      (node (ref "VT21") (pin "3") (pinfunction "D_3") (pintype "passive"))
      (node (ref "XS5") (pin "P$1") (pinfunction "1_P$1") (pintype "passive"))
      (node (ref "XS6") (pin "1") (pinfunction "1_1") (pintype "passive"))
    )
    (net (code "49") (name "Net-(DA1-ADJ)") (class "Default")
      (node (ref "DA1") (pin "1") (pinfunction "ADJ_1") (pintype "passive"))
      (node (ref "R1") (pin "1") (pinfunction "1_1") (pintype "passive"))
      (node (ref "R2") (pin "2") (pinfunction "2_2") (pintype "passive"))
    )
    (net (code "50") (name "Net-(DA2-ADJ)") (class "Default")
      (node (ref "DA2") (pin "1") (pinfunction "ADJ_1") (pintype "passive"))
      (node (ref "R15") (pin "2") (pinfunction "S_2") (pintype "passive"))
    )
    (net (code "51") (name "Net-(DA2-VI)") (class "Default")
      (node (ref "DA2") (pin "3") (pinfunction "VI_3") (pintype "input"))
      (node (ref "R12") (pin "2") (pinfunction "2_2") (pintype "passive"))
      (node (ref "R20") (pin "1") (pinfunction "1_1") (pintype "passive"))
      (node (ref "VT1") (pin "3") (pinfunction "D_3") (pintype "passive"))
    )
    (net (code "52") (name "Net-(DA3-ADJ)") (class "Default")
      (node (ref "DA3") (pin "1") (pinfunction "ADJ_1") (pintype "passive"))
      (node (ref "R16") (pin "2") (pinfunction "S_2") (pintype "passive"))
    )
    (net (code "53") (name "Net-(DA3-VI)") (class "Default")
      (node (ref "DA3") (pin "3") (pinfunction "VI_3") (pintype "input"))
      (node (ref "R14") (pin "2") (pinfunction "2_2") (pintype "passive"))
      (node (ref "R18") (pin "2") (pinfunction "2_2") (pintype "passive"))
      (node (ref "VT2") (pin "3") (pinfunction "D_3") (pintype "passive"))
    )
    (net (code "54") (name "Net-(DA4-ADJ)") (class "Default")
      (node (ref "DA4") (pin "1") (pinfunction "ADJ_1") (pintype "passive"))
      (node (ref "R45") (pin "2") (pinfunction "S_2") (pintype "passive"))
    )
    (net (code "55") (name "Net-(DA4-VI)") (class "Default")
      (node (ref "DA4") (pin "3") (pinfunction "VI_3") (pintype "input"))
      (node (ref "R39") (pin "2") (pinfunction "2_2") (pintype "passive"))
      (node (ref "R50") (pin "1") (pinfunction "1_1") (pintype "passive"))
      (node (ref "VT8") (pin "3") (pinfunction "D_3") (pintype "passive"))
    )
    (net (code "56") (name "Net-(DA5-ADJ)") (class "Default")
      (node (ref "DA5") (pin "1") (pinfunction "ADJ_1") (pintype "passive"))
      (node (ref "R46") (pin "2") (pinfunction "S_2") (pintype "passive"))
    )
    (net (code "57") (name "Net-(DA5-VI)") (class "Default")
      (node (ref "DA5") (pin "3") (pinfunction "VI_3") (pintype "input"))
      (node (ref "R41") (pin "2") (pinfunction "2_2") (pintype "passive"))
      (node (ref "R48") (pin "2") (pinfunction "2_2") (pintype "passive"))
      (node (ref "VT9") (pin "3") (pinfunction "D_3") (pintype "passive"))
    )
    (net (code "58") (name "Net-(DA6-ADJ)") (class "Default")
      (node (ref "DA6") (pin "1") (pinfunction "ADJ_1") (pintype "passive"))
      (node (ref "R72") (pin "2") (pinfunction "S_2") (pintype "passive"))
    )
    (net (code "59") (name "Net-(DA6-VI)") (class "Default")
      (node (ref "DA6") (pin "3") (pinfunction "VI_3") (pintype "input"))
      (node (ref "R69") (pin "2") (pinfunction "2_2") (pintype "passive"))
      (node (ref "R77") (pin "1") (pinfunction "1_1") (pintype "passive"))
      (node (ref "VT15") (pin "3") (pinfunction "D_3") (pintype "passive"))
    )
    (net (code "60") (name "Net-(DA7-ADJ)") (class "Default")
      (node (ref "DA7") (pin "1") (pinfunction "ADJ_1") (pintype "passive"))
      (node (ref "R73") (pin "2") (pinfunction "S_2") (pintype "passive"))
    )
    (net (code "61") (name "Net-(DA7-VI)") (class "Default")
      (node (ref "DA7") (pin "3") (pinfunction "VI_3") (pintype "input"))
      (node (ref "R71") (pin "2") (pinfunction "2_2") (pintype "passive"))
      (node (ref "R75") (pin "2") (pinfunction "2_2") (pintype "passive"))
      (node (ref "VT16") (pin "3") (pinfunction "D_3") (pintype "passive"))
    )
    (net (code "62") (name "Net-(DD1-PA8)") (class "Default")
      (node (ref "DD1") (pin "P$5") (pinfunction "PA8_P$5") (pintype "bidirectional"))
      (node (ref "JP2") (pin "3") (pinfunction "3_3") (pintype "passive"))
    )
    (net (code "63") (name "Net-(DD1-PA9)") (class "Default")
      (node (ref "DD1") (pin "P$6") (pinfunction "PA9_P$6") (pintype "bidirectional"))
      (node (ref "JP2") (pin "2") (pinfunction "2_2") (pintype "passive"))
    )
    (net (code "64") (name "Net-(DD1-PA10)") (class "Default")
      (node (ref "DD1") (pin "P$7") (pinfunction "PA10_P$7") (pintype "bidirectional"))
      (node (ref "JP2") (pin "1") (pinfunction "1_1") (pintype "passive"))
    )
    (net (code "65") (name "Net-(DD1-PB6)") (class "Default")
      (node (ref "DD1") (pin "P$14") (pinfunction "PB6_P$14") (pintype "bidirectional"))
      (node (ref "HG1") (pin "P$1") (pinfunction "CLK_P$1") (pintype "bidirectional"))
    )
    (net (code "66") (name "Net-(DD1-PB7)") (class "Default")
      (node (ref "DD1") (pin "P$15") (pinfunction "PB7_P$15") (pintype "bidirectional"))
      (node (ref "HG1") (pin "P$2") (pinfunction "DATA_P$2") (pintype "bidirectional"))
    )
    (net (code "67") (name "Net-(DD1-PB8)") (class "Default")
      (node (ref "DD1") (pin "P$16") (pinfunction "PB8_P$16") (pintype "bidirectional"))
      (node (ref "HG1") (pin "P$4") (pinfunction "CS_P$4") (pintype "bidirectional"))
    )
    (net (code "68") (name "Net-(DD1-PB9)") (class "Default")
      (node (ref "DD1") (pin "P$17") (pinfunction "PB9_P$17") (pintype "bidirectional"))
      (node (ref "HG1") (pin "P$5") (pinfunction "RESET_P$5") (pintype "bidirectional"))
    )
    (net (code "69") (name "Net-(DD1-PB15)") (class "Default")
      (node (ref "DD1") (pin "P$4") (pinfunction "PB15_P$4") (pintype "bidirectional"))
      (node (ref "JP2") (pin "4") (pinfunction "4_4") (pintype "passive"))
    )
    (net (code "70") (name "Net-(F1-Pad1)") (class "Default")
      (node (ref "F1") (pin "1") (pinfunction "1_1") (pintype "passive"))
      (node (ref "J1") (pin "1") (pinfunction "1_1") (pintype "passive"))
    )
    (net (code "71") (name "Net-(IC1A-+IN)") (class "Default")
      (node (ref "IC1") (pin "3") (pinfunction "+IN_3") (pintype "input"))
      (node (ref "R25") (pin "2") (pinfunction "2_2") (pintype "passive"))
      (node (ref "VT7") (pin "2") (pinfunction "S_2") (pintype "passive"))
    )
    (net (code "72") (name "Net-(IC1A--IN)") (class "Default")
      (node (ref "IC1") (pin "2") (pinfunction "-IN_2") (pintype "input"))
      (node (ref "R28") (pin "2") (pinfunction "2_2") (pintype "passive"))
      (node (ref "R29") (pin "1") (pinfunction "1_1") (pintype "passive"))
    )
    (net (code "73") (name "Net-(IC1B-+IN)") (class "Default")
      (node (ref "IC1") (pin "5") (pinfunction "+IN_5") (pintype "input"))
      (node (ref "R24") (pin "2") (pinfunction "2_2") (pintype "passive"))
      (node (ref "VT6") (pin "2") (pinfunction "S_2") (pintype "passive"))
    )
    (net (code "74") (name "Net-(IC1B--IN)") (class "Default")
      (node (ref "IC1") (pin "6") (pinfunction "-IN_6") (pintype "input"))
      (node (ref "R26") (pin "2") (pinfunction "2_2") (pintype "passive"))
      (node (ref "R27") (pin "1") (pinfunction "1_1") (pintype "passive"))
    )
    (net (code "75") (name "Net-(IC2A-+IN)") (class "Default")
      (node (ref "IC2") (pin "3") (pinfunction "+IN_3") (pintype "input"))
      (node (ref "R55") (pin "2") (pinfunction "2_2") (pintype "passive"))
      (node (ref "VT14") (pin "2") (pinfunction "S_2") (pintype "passive"))
    )
    (net (code "76") (name "Net-(IC2A--IN)") (class "Default")
      (node (ref "IC2") (pin "2") (pinfunction "-IN_2") (pintype "input"))
      (node (ref "R58") (pin "2") (pinfunction "2_2") (pintype "passive"))
      (node (ref "R59") (pin "1") (pinfunction "1_1") (pintype "passive"))
    )
    (net (code "77") (name "Net-(IC2B-+IN)") (class "Default")
      (node (ref "IC2") (pin "5") (pinfunction "+IN_5") (pintype "input"))
      (node (ref "R54") (pin "2") (pinfunction "2_2") (pintype "passive"))
      (node (ref "VT13") (pin "2") (pinfunction "S_2") (pintype "passive"))
    )
    (net (code "78") (name "Net-(IC2B--IN)") (class "Default")
      (node (ref "IC2") (pin "6") (pinfunction "-IN_6") (pintype "input"))
      (node (ref "R56") (pin "2") (pinfunction "2_2") (pintype "passive"))
      (node (ref "R57") (pin "1") (pinfunction "1_1") (pintype "passive"))
    )
    (net (code "79") (name "Net-(IC3A-+IN)") (class "Default")
      (node (ref "IC3") (pin "3") (pinfunction "+IN_3") (pintype "input"))
      (node (ref "R82") (pin "2") (pinfunction "2_2") (pintype "passive"))
      (node (ref "VT21") (pin "2") (pinfunction "S_2") (pintype "passive"))
    )
    (net (code "80") (name "Net-(IC3A--IN)") (class "Default")
      (node (ref "IC3") (pin "2") (pinfunction "-IN_2") (pintype "input"))
      (node (ref "R85") (pin "2") (pinfunction "2_2") (pintype "passive"))
      (node (ref "R86") (pin "1") (pinfunction "1_1") (pintype "passive"))
    )
    (net (code "81") (name "Net-(IC3B-+IN)") (class "Default")
      (node (ref "IC3") (pin "5") (pinfunction "+IN_5") (pintype "input"))
      (node (ref "R81") (pin "2") (pinfunction "2_2") (pintype "passive"))
      (node (ref "VT20") (pin "2") (pinfunction "S_2") (pintype "passive"))
    )
    (net (code "82") (name "Net-(IC3B--IN)") (class "Default")
      (node (ref "IC3") (pin "6") (pinfunction "-IN_6") (pintype "input"))
      (node (ref "R83") (pin "2") (pinfunction "2_2") (pintype "passive"))
      (node (ref "R84") (pin "1") (pinfunction "1_1") (pintype "passive"))
    )
    (net (code "83") (name "Net-(LED1-PadA)") (class "Default")
      (node (ref "LED1") (pin "A") (pinfunction "A_A") (pintype "passive"))
      (node (ref "R12") (pin "1") (pinfunction "1_1") (pintype "passive"))
    )
    (net (code "84") (name "Net-(LED2-PadA)") (class "Default")
      (node (ref "LED2") (pin "A") (pinfunction "A_A") (pintype "passive"))
      (node (ref "R14") (pin "1") (pinfunction "1_1") (pintype "passive"))
    )
    (net (code "85") (name "Net-(LED3-PadA)") (class "Default")
      (node (ref "LED3") (pin "A") (pinfunction "A_A") (pintype "passive"))
      (node (ref "R39") (pin "1") (pinfunction "1_1") (pintype "passive"))
    )
    (net (code "86") (name "Net-(LED4-PadA)") (class "Default")
      (node (ref "LED4") (pin "A") (pinfunction "A_A") (pintype "passive"))
      (node (ref "R41") (pin "1") (pinfunction "1_1") (pintype "passive"))
    )
    (net (code "87") (name "Net-(LED5-PadA)") (class "Default")
      (node (ref "LED5") (pin "A") (pinfunction "A_A") (pintype "passive"))
      (node (ref "R69") (pin "1") (pinfunction "1_1") (pintype "passive"))
    )
    (net (code "88") (name "Net-(LED6-PadA)") (class "Default")
      (node (ref "LED6") (pin "A") (pinfunction "A_A") (pintype "passive"))
      (node (ref "R71") (pin "1") (pinfunction "1_1") (pintype "passive"))
    )
    (net (code "89") (name "Net-(R10B-2)") (class "Default")
      (node (ref "R10") (pin "4") (pinfunction "2_4") (pintype "passive"))
      (node (ref "SA5") (pin "1$P") (pinfunction "P_1$P") (pintype "passive"))
    )
    (net (code "90") (name "Net-(R15-E)") (class "Default")
      (node (ref "R11") (pin "1") (pinfunction "1_1") (pintype "passive"))
      (node (ref "R15") (pin "3") (pinfunction "E_3") (pintype "passive"))
    )
    (net (code "91") (name "Net-(R16-E)") (class "Default")
      (node (ref "R13") (pin "1") (pinfunction "1_1") (pintype "passive"))
      (node (ref "R16") (pin "3") (pinfunction "E_3") (pintype "passive"))
    )
    (net (code "92") (name "Net-(R19-Pad1)") (class "Default")
      (node (ref "R19") (pin "1") (pinfunction "1_1") (pintype "passive"))
      (node (ref "R21") (pin "2") (pinfunction "2_2") (pintype "passive"))
    )
    (net (code "93") (name "Net-(R37B-2)") (class "Default")
      (node (ref "R37") (pin "4") (pinfunction "2_4") (pintype "passive"))
      (node (ref "SA10") (pin "1$P") (pinfunction "P_1$P") (pintype "passive"))
    )
    (net (code "94") (name "Net-(R45-E)") (class "Default")
      (node (ref "R38") (pin "1") (pinfunction "1_1") (pintype "passive"))
      (node (ref "R45") (pin "3") (pinfunction "E_3") (pintype "passive"))
    )
    (net (code "95") (name "Net-(R46-E)") (class "Default")
      (node (ref "R40") (pin "1") (pinfunction "1_1") (pintype "passive"))
      (node (ref "R46") (pin "3") (pinfunction "E_3") (pintype "passive"))
    )
    (net (code "96") (name "Net-(R49-Pad1)") (class "Default")
      (node (ref "R49") (pin "1") (pinfunction "1_1") (pintype "passive"))
      (node (ref "R51") (pin "2") (pinfunction "2_2") (pintype "passive"))
    )
    (net (code "97") (name "Net-(R67B-2)") (class "Default")
      (node (ref "R67") (pin "4") (pinfunction "2_4") (pintype "passive"))
      (node (ref "SA15") (pin "1$P") (pinfunction "P_1$P") (pintype "passive"))
    )
    (net (code "98") (name "Net-(R72-E)") (class "Default")
      (node (ref "R68") (pin "1") (pinfunction "1_1") (pintype "passive"))
      (node (ref "R72") (pin "3") (pinfunction "E_3") (pintype "passive"))
    )
    (net (code "99") (name "Net-(R73-E)") (class "Default")
      (node (ref "R70") (pin "1") (pinfunction "1_1") (pintype "passive"))
      (node (ref "R73") (pin "3") (pinfunction "E_3") (pintype "passive"))
    )
    (net (code "100") (name "Net-(R76-Pad1)") (class "Default")
      (node (ref "R76") (pin "1") (pinfunction "1_1") (pintype "passive"))
      (node (ref "R78") (pin "2") (pinfunction "2_2") (pintype "passive"))
    )
    (net (code "101") (name "Net-(SA1-P)") (class "Default")
      (node (ref "F1") (pin "2") (pinfunction "2_2") (pintype "passive"))
      (node (ref "SA1") (pin "3") (pinfunction "P_3") (pintype "passive"))
    )
    (net (code "102") (name "Net-(SA2-S)") (class "Default")
      (node (ref "C6") (pin "1") (pinfunction "1_1") (pintype "passive"))
      (node (ref "SA2") (pin "1$S") (pinfunction "S_1$S") (pintype "passive"))
      (node (ref "SA4") (pin "1$P") (pinfunction "P_1$P") (pintype "passive"))
    )
    (net (code "103") (name "Net-(SA3-P)") (class "Default")
      (node (ref "R10") (pin "2") (pinfunction "2_2") (pintype "passive"))
      (node (ref "SA3") (pin "1$P") (pinfunction "P_1$P") (pintype "passive"))
    )
    (net (code "104") (name "Net-(SA3-S)") (class "Default")
      (node (ref "SA3") (pin "1$S") (pinfunction "S_1$S") (pintype "passive"))
      (node (ref "SA5") (pin "1$S") (pinfunction "S_1$S") (pintype "passive"))
      (node (ref "XS1") (pin "P$2") (pinfunction "2_P$2") (pintype "passive"))
      (node (ref "XS2") (pin "2") (pinfunction "2_2") (pintype "passive"))
    )
    (net (code "105") (name "Net-(SA4-O)") (class "Default")
      (node (ref "R8") (pin "1") (pinfunction "1_1") (pintype "passive"))
      (node (ref "SA4") (pin "1$O") (pinfunction "O_1$O") (pintype "passive"))
    )
    (net (code "106") (name "Net-(SA7-S)") (class "Default")
      (node (ref "C10") (pin "1") (pinfunction "1_1") (pintype "passive"))
      (node (ref "SA7") (pin "1$S") (pinfunction "S_1$S") (pintype "passive"))
      (node (ref "SA9") (pin "1$P") (pinfunction "P_1$P") (pintype "passive"))
    )
    (net (code "107") (name "Net-(SA8-P)") (class "Default")
      (node (ref "R37") (pin "2") (pinfunction "2_2") (pintype "passive"))
      (node (ref "SA8") (pin "1$P") (pinfunction "P_1$P") (pintype "passive"))
    )
    (net (code "108") (name "Net-(SA9-O)") (class "Default")
      (node (ref "R35") (pin "1") (pinfunction "1_1") (pintype "passive"))
      (node (ref "SA9") (pin "1$O") (pinfunction "O_1$O") (pintype "passive"))
    )
    (net (code "109") (name "Net-(SA10-S)") (class "Default")
      (node (ref "SA10") (pin "1$S") (pinfunction "S_1$S") (pintype "passive"))
      (node (ref "SA8") (pin "1$S") (pinfunction "S_1$S") (pintype "passive"))
      (node (ref "XS3") (pin "P$2") (pinfunction "2_P$2") (pintype "passive"))
      (node (ref "XS4") (pin "2") (pinfunction "2_2") (pintype "passive"))
    )
    (net (code "110") (name "Net-(SA12-S)") (class "Default")
      (node (ref "C14") (pin "1") (pinfunction "1_1") (pintype "passive"))
      (node (ref "SA12") (pin "1$S") (pinfunction "S_1$S") (pintype "passive"))
      (node (ref "SA14") (pin "1$P") (pinfunction "P_1$P") (pintype "passive"))
    )
    (net (code "111") (name "Net-(SA13-P)") (class "Default")
      (node (ref "R67") (pin "2") (pinfunction "2_2") (pintype "passive"))
      (node (ref "SA13") (pin "1$P") (pinfunction "P_1$P") (pintype "passive"))
    )
    (net (code "112") (name "Net-(SA13-S)") (class "Default")
      (node (ref "SA13") (pin "1$S") (pinfunction "S_1$S") (pintype "passive"))
      (node (ref "SA15") (pin "1$S") (pinfunction "S_1$S") (pintype "passive"))
      (node (ref "XS5") (pin "P$2") (pinfunction "2_P$2") (pintype "passive"))
      (node (ref "XS6") (pin "2") (pinfunction "2_2") (pintype "passive"))
    )
    (net (code "113") (name "Net-(SA14-O)") (class "Default")
      (node (ref "R65") (pin "1") (pinfunction "1_1") (pintype "passive"))
      (node (ref "SA14") (pin "1$O") (pinfunction "O_1$O") (pintype "passive"))
    )
    (net (code "114") (name "Net-(VT1-G)") (class "Default")
      (node (ref "R3") (pin "1") (pinfunction "1_1") (pintype "passive"))
      (node (ref "VT1") (pin "1") (pinfunction "G_1") (pintype "passive"))
      (node (ref "VT3") (pin "1") (pinfunction "C_1") (pintype "passive"))
    )
    (net (code "115") (name "Net-(VT2-G)") (class "Default")
      (node (ref "R4") (pin "1") (pinfunction "1_1") (pintype "passive"))
      (node (ref "VT2") (pin "1") (pinfunction "G_1") (pintype "passive"))
      (node (ref "VT5") (pin "1") (pinfunction "C_1") (pintype "passive"))
    )
    (net (code "116") (name "Net-(VT4-B)") (class "Default")
      (node (ref "R9") (pin "1") (pinfunction "1_1") (pintype "passive"))
      (node (ref "VT4") (pin "2") (pinfunction "B_2") (pintype "passive"))
    )
    (net (code "117") (name "Net-(VT6-G)") (class "Default")
      (node (ref "R18") (pin "1") (pinfunction "1_1") (pintype "passive"))
      (node (ref "R22") (pin "2") (pinfunction "2_2") (pintype "passive"))
      (node (ref "VT6") (pin "1") (pinfunction "G_1") (pintype "passive"))
    )
    (net (code "118") (name "Net-(VT7-G)") (class "Default")
      (node (ref "R20") (pin "2") (pinfunction "2_2") (pintype "passive"))
      (node (ref "R23") (pin "2") (pinfunction "2_2") (pintype "passive"))
      (node (ref "VT7") (pin "1") (pinfunction "G_1") (pintype "passive"))
    )
    (net (code "119") (name "Net-(VT10-C)") (class "Default")
      (node (ref "R30") (pin "1") (pinfunction "1_1") (pintype "passive"))
      (node (ref "VT10") (pin "1") (pinfunction "C_1") (pintype "passive"))
      (node (ref "VT8") (pin "1") (pinfunction "G_1") (pintype "passive"))
    )
    (net (code "120") (name "Net-(VT11-B)") (class "Default")
      (node (ref "R36") (pin "1") (pinfunction "1_1") (pintype "passive"))
      (node (ref "VT11") (pin "2") (pinfunction "B_2") (pintype "passive"))
    )
    (net (code "121") (name "Net-(VT12-C)") (class "Default")
      (node (ref "R31") (pin "1") (pinfunction "1_1") (pintype "passive"))
      (node (ref "VT12") (pin "1") (pinfunction "C_1") (pintype "passive"))
      (node (ref "VT9") (pin "1") (pinfunction "G_1") (pintype "passive"))
    )
    (net (code "122") (name "Net-(VT13-G)") (class "Default")
      (node (ref "R48") (pin "1") (pinfunction "1_1") (pintype "passive"))
      (node (ref "R52") (pin "2") (pinfunction "2_2") (pintype "passive"))
      (node (ref "VT13") (pin "1") (pinfunction "G_1") (pintype "passive"))
    )
    (net (code "123") (name "Net-(VT14-G)") (class "Default")
      (node (ref "R50") (pin "2") (pinfunction "2_2") (pintype "passive"))
      (node (ref "R53") (pin "2") (pinfunction "2_2") (pintype "passive"))
      (node (ref "VT14") (pin "1") (pinfunction "G_1") (pintype "passive"))
    )
    (net (code "124") (name "Net-(VT15-G)") (class "Default")
      (node (ref "R60") (pin "1") (pinfunction "1_1") (pintype "passive"))
      (node (ref "VT15") (pin "1") (pinfunction "G_1") (pintype "passive"))
      (node (ref "VT17") (pin "1") (pinfunction "C_1") (pintype "passive"))
    )
    (net (code "125") (name "Net-(VT16-G)") (class "Default")
      (node (ref "R61") (pin "1") (pinfunction "1_1") (pintype "passive"))
      (node (ref "VT16") (pin "1") (pinfunction "G_1") (pintype "passive"))
      (node (ref "VT19") (pin "1") (pinfunction "C_1") (pintype "passive"))
    )
    (net (code "126") (name "Net-(VT18-B)") (class "Default")
      (node (ref "R66") (pin "1") (pinfunction "1_1") (pintype "passive"))
      (node (ref "VT18") (pin "2") (pinfunction "B_2") (pintype "passive"))
    )
    (net (code "127") (name "Net-(VT20-G)") (class "Default")
      (node (ref "R75") (pin "1") (pinfunction "1_1") (pintype "passive"))
      (node (ref "R79") (pin "2") (pinfunction "2_2") (pintype "passive"))
      (node (ref "VT20") (pin "1") (pinfunction "G_1") (pintype "passive"))
    )
    (net (code "128") (name "Net-(VT21-G)") (class "Default")
      (node (ref "R77") (pin "2") (pinfunction "2_2") (pintype "passive"))
      (node (ref "R80") (pin "2") (pinfunction "2_2") (pintype "passive"))
      (node (ref "VT21") (pin "1") (pinfunction "G_1") (pintype "passive"))
    )
    (net (code "129") (name "VCC") (class "Default")
      (node (ref "C2") (pin "+") (pinfunction "+_+") (pintype "passive"))
      (node (ref "DA1") (pin "2") (pinfunction "VO_2") (pintype "passive"))
      (node (ref "DD1") (pin "P$20") (pinfunction "3.3V1_P$20") (pintype "bidirectional"))
      (node (ref "DD1") (pin "P$23") (pinfunction "3.3V_P$23") (pintype "bidirectional"))
      (node (ref "HG1") (pin "P$10") (pinfunction "VCC_P$10") (pintype "bidirectional"))
      (node (ref "HG1") (pin "P$6") (pinfunction "LED+_P$6") (pintype "bidirectional"))
      (node (ref "HG1") (pin "P$9") (pinfunction "VCC_P$9") (pintype "bidirectional"))
      (node (ref "R1") (pin "2") (pinfunction "2_2") (pintype "passive"))
      (node (ref "R17") (pin "1") (pinfunction "1_1") (pintype "passive"))
      (node (ref "R19") (pin "3") (pinfunction "2_3") (pintype "passive"))
      (node (ref "R32") (pin "2") (pinfunction "2_2") (pintype "passive"))
      (node (ref "R33") (pin "2") (pinfunction "2_2") (pintype "passive"))
      (node (ref "R34") (pin "2") (pinfunction "2_2") (pintype "passive"))
      (node (ref "R35") (pin "2") (pinfunction "2_2") (pintype "passive"))
      (node (ref "R47") (pin "1") (pinfunction "1_1") (pintype "passive"))
      (node (ref "R49") (pin "3") (pinfunction "2_3") (pintype "passive"))
      (node (ref "R5") (pin "2") (pinfunction "2_2") (pintype "passive"))
      (node (ref "R6") (pin "2") (pinfunction "2_2") (pintype "passive"))
      (node (ref "R62") (pin "2") (pinfunction "2_2") (pintype "passive"))
      (node (ref "R63") (pin "2") (pinfunction "2_2") (pintype "passive"))
      (node (ref "R64") (pin "2") (pinfunction "2_2") (pintype "passive"))
      (node (ref "R65") (pin "2") (pinfunction "2_2") (pintype "passive"))
      (node (ref "R7") (pin "2") (pinfunction "2_2") (pintype "passive"))
      (node (ref "R74") (pin "1") (pinfunction "1_1") (pintype "passive"))
      (node (ref "R76") (pin "3") (pinfunction "2_3") (pintype "passive"))
      (node (ref "R8") (pin "2") (pinfunction "2_2") (pintype "passive"))
      (node (ref "S1") (pin "4") (pinfunction "4_4") (pintype "passive"))
      (node (ref "S1") (pin "5") (pinfunction "5_5") (pintype "passive"))
      (node (ref "S1") (pin "6") (pinfunction "6_6") (pintype "passive"))
    )
    (net (code "130") (name "unconnected-(DD1-5V-PadP$18)") (class "Default")
      (node (ref "DD1") (pin "P$18") (pinfunction "5V_P$18") (pintype "bidirectional"))
    )
    (net (code "131") (name "unconnected-(DD1-PC13-PadP$39)") (class "Default")
      (node (ref "DD1") (pin "P$39") (pinfunction "PC13_P$39") (pintype "bidirectional"))
    )
    (net (code "132") (name "unconnected-(DD1-PC14-PadP$38)") (class "Default")
      (node (ref "DD1") (pin "P$38") (pinfunction "PC14_P$38") (pintype "bidirectional"))
    )
    (net (code "133") (name "unconnected-(DD1-PC15-PadP$37)") (class "Default")
      (node (ref "DD1") (pin "P$37") (pinfunction "PC15_P$37") (pintype "bidirectional"))
    )
    (net (code "134") (name "unconnected-(DD1-RESET-PadP$24)") (class "Default")
      (node (ref "DD1") (pin "P$24") (pinfunction "RESET_P$24") (pintype "bidirectional"))
    )
    (net (code "135") (name "unconnected-(DD1-VBAT-PadP$40)") (class "Default")
      (node (ref "DD1") (pin "P$40") (pinfunction "VBAT_P$40") (pintype "bidirectional"))
    )
    (net (code "136") (name "unconnected-(HG1-N{slash}A-PadP$8)") (class "Default")
      (node (ref "HG1") (pin "P$8") (pinfunction "N/A_P$8") (pintype "bidirectional"))
    )
    (net (code "137") (name "unconnected-(J1-Pad2)") (class "Default")
      (node (ref "J1") (pin "2") (pinfunction "2_2") (pintype "passive"))
    )
    (net (code "138") (name "unconnected-(SA1-S-Pad2)") (class "Default")
      (node (ref "SA1") (pin "2") (pinfunction "S_2") (pintype "passive"))
    )
    (net (code "139") (name "unconnected-(SA3-O-Pad1$O)") (class "Default")
      (node (ref "SA3") (pin "1$O") (pinfunction "O_1$O") (pintype "passive"))
    )
    (net (code "140") (name "unconnected-(SA5-O-Pad1$O)") (class "Default")
      (node (ref "SA5") (pin "1$O") (pinfunction "O_1$O") (pintype "passive"))
    )
    (net (code "141") (name "unconnected-(SA8-O-Pad1$O)") (class "Default")
      (node (ref "SA8") (pin "1$O") (pinfunction "O_1$O") (pintype "passive"))
    )
    (net (code "142") (name "unconnected-(SA10-O-Pad1$O)") (class "Default")
      (node (ref "SA10") (pin "1$O") (pinfunction "O_1$O") (pintype "passive"))
    )
    (net (code "143") (name "unconnected-(SA13-O-Pad1$O)") (class "Default")
      (node (ref "SA13") (pin "1$O") (pinfunction "O_1$O") (pintype "passive"))
    )
    (net (code "144") (name "unconnected-(SA15-O-Pad1$O)") (class "Default")
      (node (ref "SA15") (pin "1$O") (pinfunction "O_1$O") (pintype "passive"))
    )
  )
)
